# design.net
KiCad netlist of a schematic drawn in EasyEDA Pro
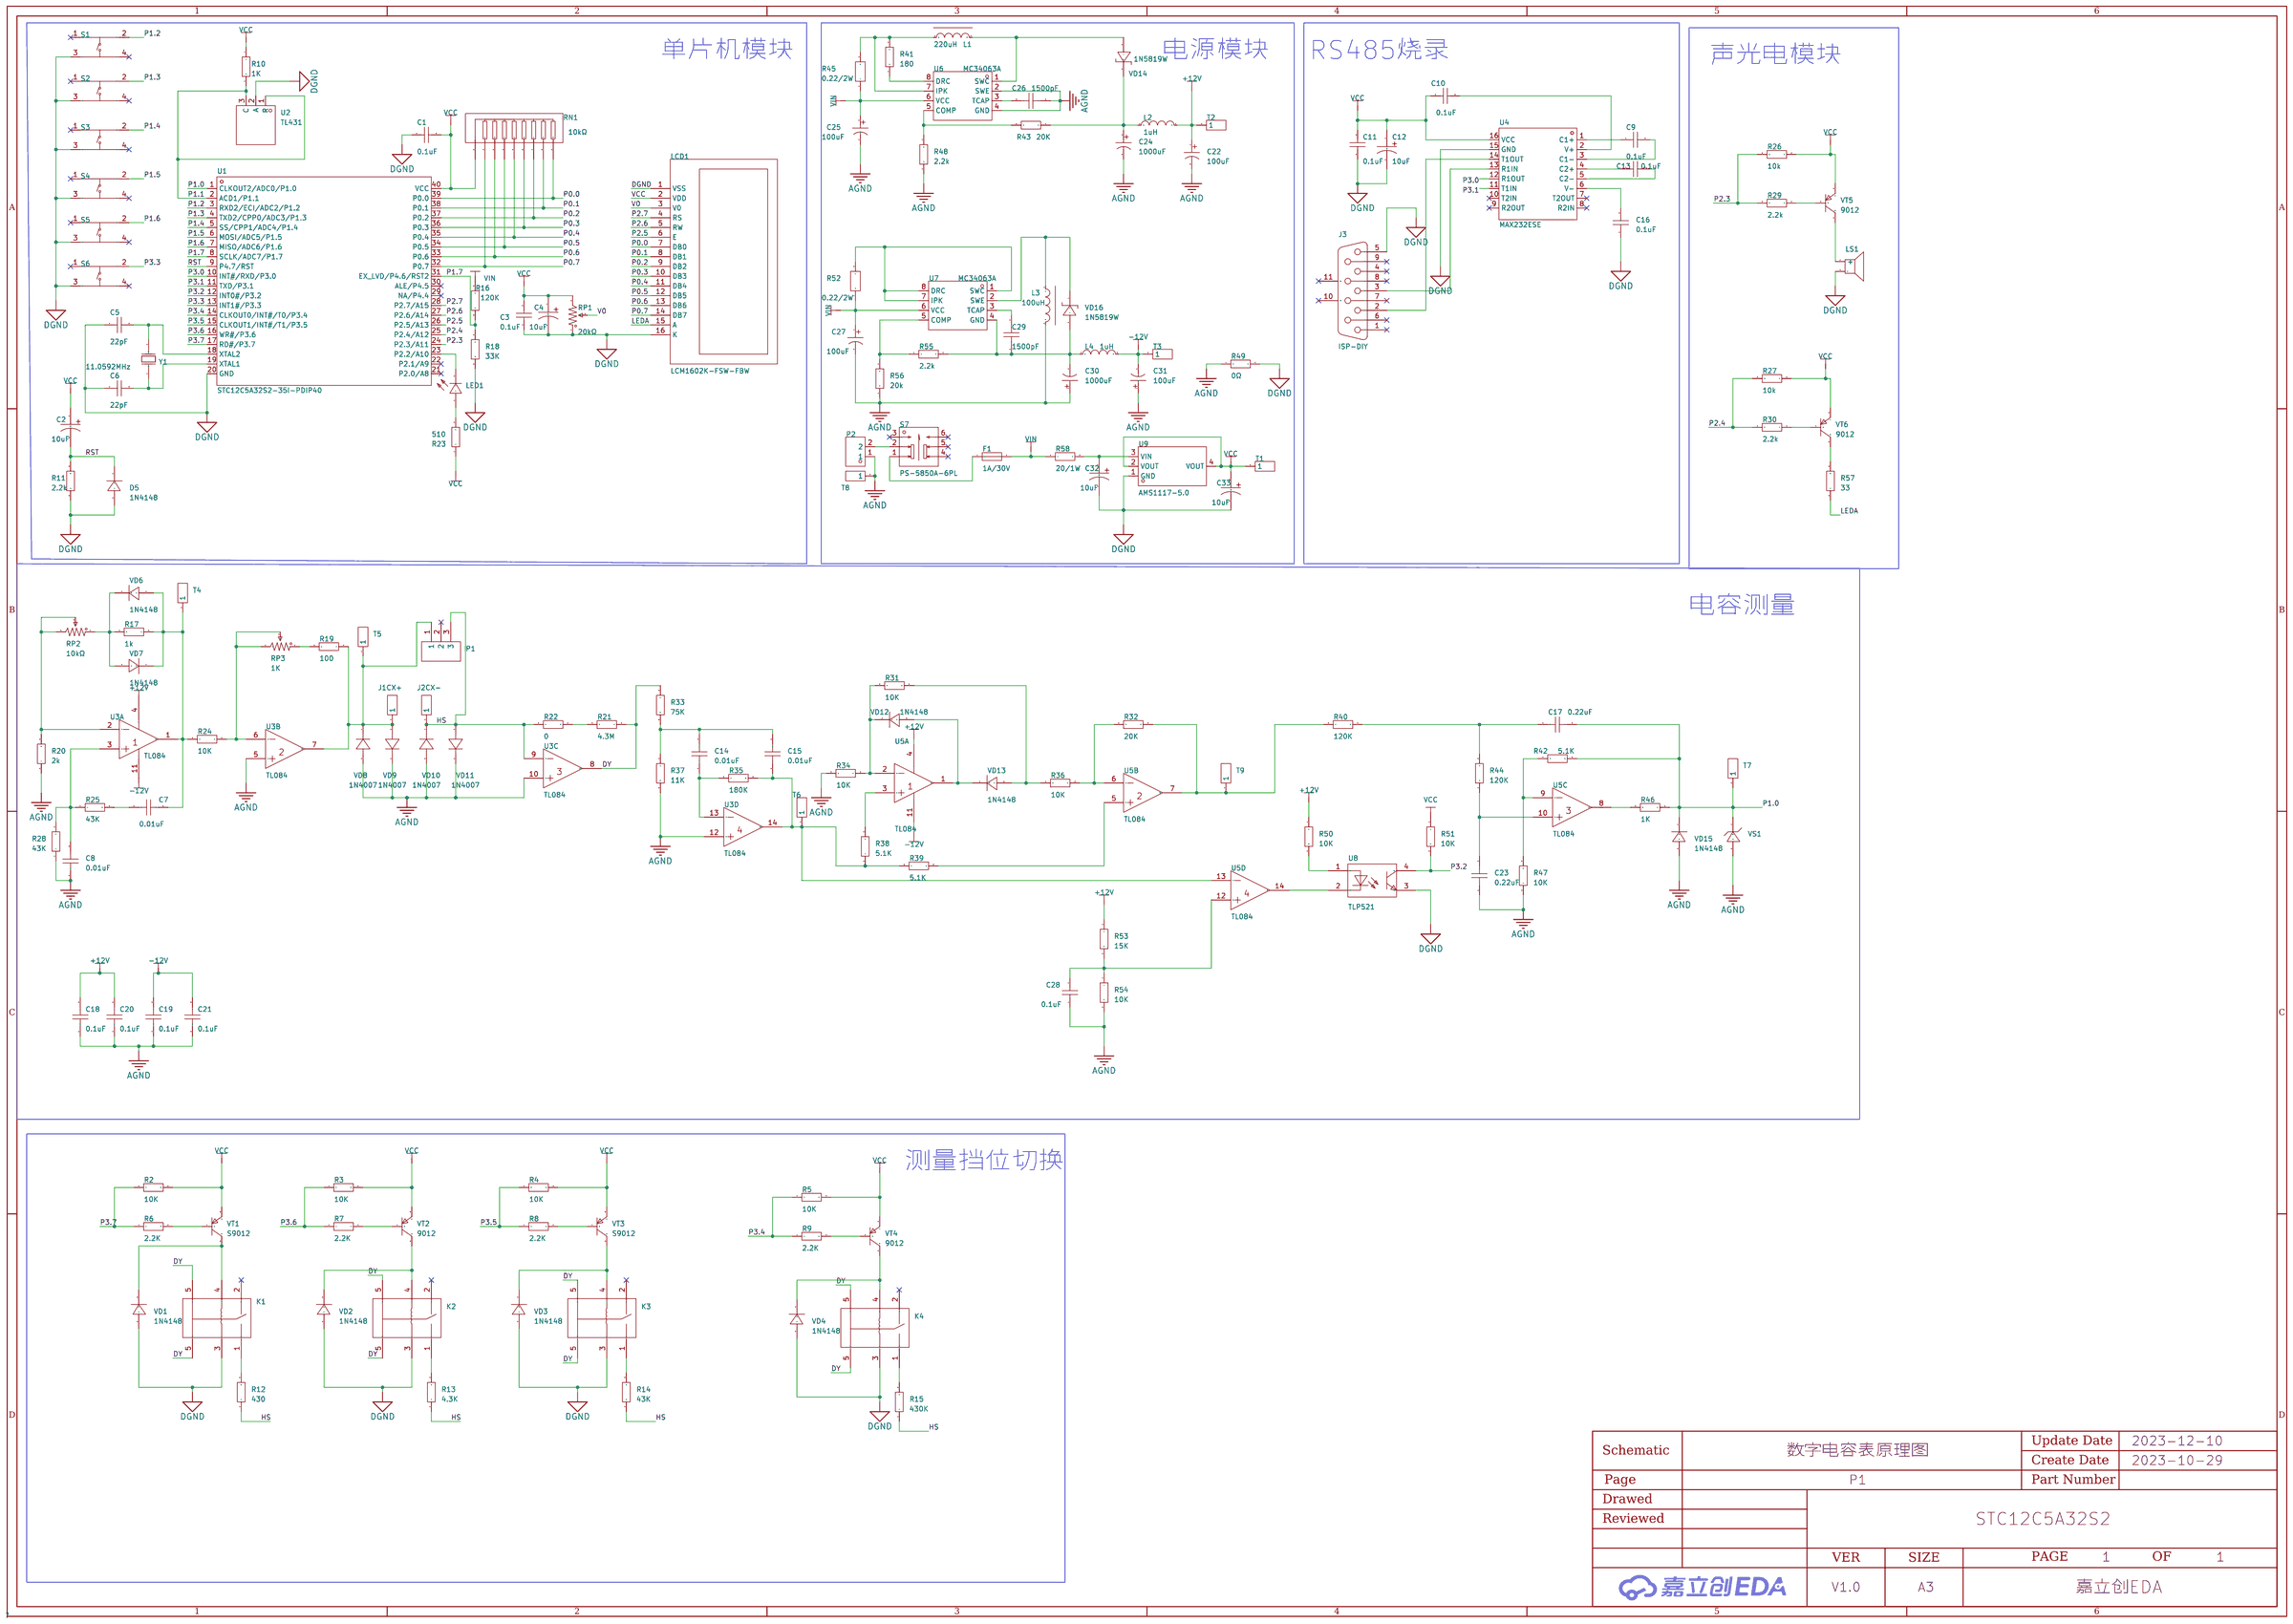
[diagram p0: schematic sheet]

(export (version "E")
  (design (tool "Eeschema 10.0.6"))
  (components
    (comp (ref "C1")
      (value "0.1uF")
      (footprint "easyedapro:C0805")
      (description "容值:100nF;精度:±10%;额定电压:50V;材质(温度系数):X7R;")
      (fields (field (name "Manufacturer Part") "C1608NP01H220J080AA") (field (name "Manufacturer") "TDK"))
      (libsource (lib "easyedapro") (part "0805B104K500NT"))
    )
    (comp (ref "C2")
      (value "10uF")
      (footprint "easyedapro:CAP-SMD_L3.2-W1.6")
      (description "容值:47uF;精度:±20%;额定电压:10V;等效串联电阻:2Ω@100kHz;")
      (fields (field (name "Manufacturer Part") "F931A476MAA") (field (name "Manufacturer") "Kyocera AVX"))
      (libsource (lib "easyedapro") (part "F931A476MAA"))
    )
    (comp (ref "C3")
      (value "0.1uF")
      (footprint "easyedapro:C0805")
      (description "容值:100nF;精度:±10%;额定电压:50V;材质(温度系数):X7R;")
      (fields (field (name "Manufacturer Part") "C1608NP01H220J080AA") (field (name "Manufacturer") "TDK"))
      (libsource (lib "easyedapro") (part "0805B104K500NT"))
    )
    (comp (ref "C4")
      (value "10uF")
      (footprint "easyedapro:CAP-SMD_L3.2-W1.6")
      (description "容值:47uF;精度:±20%;额定电压:10V;等效串联电阻:2Ω@100kHz;")
      (fields (field (name "Manufacturer Part") "F931A476MAA") (field (name "Manufacturer") "Kyocera AVX"))
      (libsource (lib "easyedapro") (part "F931A476MAA"))
    )
    (comp (ref "C5")
      (value "22pF")
      (footprint "easyedapro:C0805")
      (description "容值:100nF;精度:±10%;额定电压:50V;材质(温度系数):X7R;")
      (fields (field (name "Manufacturer Part") "C1608NP01H220J080AA") (field (name "Manufacturer") "TDK"))
      (libsource (lib "easyedapro") (part "0805B104K500NT"))
    )
    (comp (ref "C6")
      (value "22pF")
      (footprint "easyedapro:C0805")
      (description "容值:100nF;精度:±10%;额定电压:50V;材质(温度系数):X7R;")
      (fields (field (name "Manufacturer Part") "C1608NP01H220J080AA") (field (name "Manufacturer") "TDK"))
      (libsource (lib "easyedapro") (part "0805B104K500NT"))
    )
    (comp (ref "C7")
      (value "0.01uF")
      (footprint "easyedapro:CAP-TH_L13.0-W5.0-P10.00-D0.6")
      (description "容值:10nF;精度:±5%;额定电压:630V;")
      (fields
        (field (name "Manufacturer Part") "B1030630-D-10-3R")
        (field (name "Manufacturer") "GDHY(广东华裕)")
      )
      (libsource (lib "easyedapro") (part "B1030630-D-10-3R"))
    )
    (comp (ref "C8")
      (value "0.01uF")
      (footprint "easyedapro:CAP-TH_L10.3-W4.3-P7.50-D1.0")
      (description "容值:10nF;精度:±5%;额定电压:250V;")
      (fields (field (name "Manufacturer Part") "ECQE2103JF") (field (name "Manufacturer") "PANASONIC(松下)"))
      (libsource (lib "easyedapro") (part "ECQE2103JF"))
    )
    (comp (ref "C9")
      (value "0.1uF")
      (footprint "easyedapro:C0805")
      (description "容值:100nF;精度:±10%;额定电压:50V;材质(温度系数):X7R;")
      (fields (field (name "Manufacturer Part") "C1608NP01H220J080AA") (field (name "Manufacturer") "TDK"))
      (libsource (lib "easyedapro") (part "0805B104K500NT"))
    )
    (comp (ref "C10")
      (value "0.1uF")
      (footprint "easyedapro:C0805")
      (description "容值:100nF;精度:±10%;额定电压:50V;材质(温度系数):X7R;")
      (fields (field (name "Manufacturer Part") "C1608NP01H220J080AA") (field (name "Manufacturer") "TDK"))
      (libsource (lib "easyedapro") (part "0805B104K500NT"))
    )
    (comp (ref "C11")
      (value "0.1uF")
      (footprint "easyedapro:C0805")
      (description "容值:100nF;精度:±10%;额定电压:50V;材质(温度系数):X7R;")
      (fields (field (name "Manufacturer Part") "C1608NP01H220J080AA") (field (name "Manufacturer") "TDK"))
      (libsource (lib "easyedapro") (part "0805B104K500NT"))
    )
    (comp (ref "C12")
      (value "10uF")
      (footprint "easyedapro:CAP-SMD_L3.2-W1.6")
      (description "容值:47uF;精度:±20%;额定电压:10V;等效串联电阻:2Ω@100kHz;")
      (fields (field (name "Manufacturer Part") "F931A476MAA") (field (name "Manufacturer") "Kyocera AVX"))
      (libsource (lib "easyedapro") (part "F931A476MAA"))
    )
    (comp (ref "C13")
      (value "0.1uF")
      (footprint "easyedapro:C0805")
      (description "容值:100nF;精度:±10%;额定电压:50V;材质(温度系数):X7R;")
      (fields (field (name "Manufacturer Part") "C1608NP01H220J080AA") (field (name "Manufacturer") "TDK"))
      (libsource (lib "easyedapro") (part "0805B104K500NT"))
    )
    (comp (ref "C14")
      (value "0.01uF")
      (footprint "easyedapro:CAP-TH_L29.0-W17.5-P27.50-D0.8")
      (description "容值:10uF;精度:±5%;额定电压:250V;")
      (fields (field (name "Manufacturer Part") "KP106J2E2701") (field (name "Manufacturer") "KYET(科雅)"))
      (libsource (lib "easyedapro") (part "KP106J2E2701"))
    )
    (comp (ref "C15")
      (value "0.01uF")
      (footprint "easyedapro:CAP-TH_L29.0-W17.5-P27.50-D0.8")
      (description "容值:10uF;精度:±5%;额定电压:250V;")
      (fields (field (name "Manufacturer Part") "KP106J2E2701") (field (name "Manufacturer") "KYET(科雅)"))
      (libsource (lib "easyedapro") (part "KP106J2E2701"))
    )
    (comp (ref "C16")
      (value "0.1uF")
      (footprint "easyedapro:C0805")
      (description "容值:100nF;精度:±10%;额定电压:50V;材质(温度系数):X7R;")
      (fields (field (name "Manufacturer Part") "C1608NP01H220J080AA") (field (name "Manufacturer") "TDK"))
      (libsource (lib "easyedapro") (part "0805B104K500NT"))
    )
    (comp (ref "C17")
      (value "0.22uF")
      (footprint "easyedapro:CAP-TH_L29.0-W17.5-P27.50-D0.8")
      (description "容值:10uF;精度:±5%;额定电压:250V;")
      (fields (field (name "Manufacturer Part") "KP106J2E2701") (field (name "Manufacturer") "KYET(科雅)"))
      (libsource (lib "easyedapro") (part "KP106J2E2701"))
    )
    (comp (ref "C18")
      (value "0.1uF")
      (footprint "easyedapro:C0603")
      (description "容值:22pF;额定电压:50V;材质(温度系数):C0G;")
      (fields (field (name "Manufacturer Part") "0805B104K500NT") (field (name "Manufacturer") "FH(风华)"))
      (libsource (lib "easyedapro") (part "C1608NP01H220J080AA"))
    )
    (comp (ref "C19")
      (value "0.1uF")
      (footprint "easyedapro:C0603")
      (description "容值:22pF;额定电压:50V;材质(温度系数):C0G;")
      (fields (field (name "Manufacturer Part") "0805B104K500NT") (field (name "Manufacturer") "FH(风华)"))
      (libsource (lib "easyedapro") (part "C1608NP01H220J080AA"))
    )
    (comp (ref "C20")
      (value "0.1uF")
      (footprint "easyedapro:C0603")
      (description "容值:22pF;额定电压:50V;材质(温度系数):C0G;")
      (fields (field (name "Manufacturer Part") "0805B104K500NT") (field (name "Manufacturer") "FH(风华)"))
      (libsource (lib "easyedapro") (part "C1608NP01H220J080AA"))
    )
    (comp (ref "C21")
      (value "0.1uF")
      (footprint "easyedapro:C0603")
      (description "容值:22pF;额定电压:50V;材质(温度系数):C0G;")
      (fields (field (name "Manufacturer Part") "0805B104K500NT") (field (name "Manufacturer") "FH(风华)"))
      (libsource (lib "easyedapro") (part "C1608NP01H220J080AA"))
    )
    (comp (ref "C22")
      (value "100uF")
      (footprint "easyedapro:CAP-TH_BD13.0-P5.00-D1.2-FD")
      (description "容值:1000uF;精度:±20%;额定电压:35V;")
      (fields
        (field (name "Manufacturer Part") "35YXJ1000M12.5X20")
        (field (name "Manufacturer") "rubycon(红宝石)")
      )
      (libsource (lib "easyedapro") (part "35YXJ1000M12.5X20"))
    )
    (comp (ref "C23")
      (value "0.22uF")
      (footprint "easyedapro:CAP-TH_L29.0-W17.5-P27.50-D0.8")
      (description "容值:10uF;精度:±5%;额定电压:250V;")
      (fields (field (name "Manufacturer Part") "KP106J2E2701") (field (name "Manufacturer") "KYET(科雅)"))
      (libsource (lib "easyedapro") (part "KP106J2E2701"))
    )
    (comp (ref "C24")
      (value "1000uF")
      (footprint "easyedapro:CAP-TH_BD13.0-P5.00-D1.2-FD")
      (description "容值:1000uF;精度:±20%;额定电压:35V;")
      (fields
        (field (name "Manufacturer Part") "35YXJ1000M12.5X20")
        (field (name "Manufacturer") "rubycon(红宝石)")
      )
      (libsource (lib "easyedapro") (part "35YXJ1000M12.5X20"))
    )
    (comp (ref "C25")
      (value "100uF")
      (footprint "easyedapro:CAP-TH_BD13.0-P5.00-D1.2-FD")
      (description "容值:1000uF;精度:±20%;额定电压:35V;")
      (fields
        (field (name "Manufacturer Part") "35YXJ1000M12.5X20")
        (field (name "Manufacturer") "rubycon(红宝石)")
      )
      (libsource (lib "easyedapro") (part "35YXJ1000M12.5X20"))
    )
    (comp (ref "C26")
      (value "1500pF")
      (footprint "easyedapro:CAP-TH_L8.5-W5.0-P5.00-D1.2")
      (description "容值:100nF;精度:±10%;额定电压:250V;温度系数:X7R;")
      (fields (field (name "Manufacturer Part") "CT4-1206B104K251F3") (field (name "Manufacturer") "FH(风华)"))
      (libsource (lib "easyedapro") (part "CT4-1206B104K251F3"))
    )
    (comp (ref "C27")
      (value "100uF")
      (footprint "easyedapro:CAP-TH_BD6.3-P2.50-D1.0-FD")
      (description "容值:100uF;精度:±20%;额定电压:25V;纹波电流:95mA@120Hz;等效串联电阻:-;")
      (fields
        (field (name "Manufacturer Part") "KS107M025E07RR0VH2FP0")
        (field (name "Manufacturer") "CX(承兴)")
      )
      (libsource (lib "easyedapro") (part "100uF 25V 6.3*7"))
    )
    (comp (ref "C28")
      (value "0.1uF")
      (footprint "easyedapro:C0805")
      (description "容值:100nF;精度:±10%;额定电压:50V;材质(温度系数):X7R;")
      (fields (field (name "Manufacturer Part") "C1608NP01H220J080AA") (field (name "Manufacturer") "TDK"))
      (libsource (lib "easyedapro") (part "0805B104K500NT"))
    )
    (comp (ref "C29")
      (value "1500pF")
      (footprint "easyedapro:CAP-TH_L8.5-W5.0-P5.00-D1.2")
      (description "容值:100nF;精度:±10%;额定电压:250V;温度系数:X7R;")
      (fields (field (name "Manufacturer Part") "CT4-1206B104K251F3") (field (name "Manufacturer") "FH(风华)"))
      (libsource (lib "easyedapro") (part "CT4-1206B104K251F3"))
    )
    (comp (ref "C30")
      (value "1000uF")
      (footprint "easyedapro:CAP-TH_BD10.0-P5.00-D1.0-FD")
      (description "容值:1000uF;精度:±20%;额定电压:25V;纹波电流:870mA@120Hz;等效串联电阻:-;")
      (fields
        (field (name "Manufacturer Part") "25PK1000MEFC10*16")
        (field (name "Manufacturer") "rubycon(红宝石)")
      )
      (libsource (lib "easyedapro") (part "25PK1000MEFC10*16"))
    )
    (comp (ref "C31")
      (value "100uF")
      (footprint "easyedapro:CAP-TH_BD13.0-P5.00-D1.2-FD")
      (description "容值:1000uF;精度:±20%;额定电压:35V;")
      (fields
        (field (name "Manufacturer Part") "35YXJ1000M12.5X20")
        (field (name "Manufacturer") "rubycon(红宝石)")
      )
      (libsource (lib "easyedapro") (part "35YXJ1000M12.5X20"))
    )
    (comp (ref "C32")
      (value "10uF")
      (footprint "easyedapro:CAP-SMD_L3.2-W1.6")
      (description "容值:47uF;精度:±20%;额定电压:10V;等效串联电阻:2Ω@100kHz;")
      (fields (field (name "Manufacturer Part") "F931A476MAA") (field (name "Manufacturer") "Kyocera AVX"))
      (libsource (lib "easyedapro") (part "F931A476MAA"))
    )
    (comp (ref "C33")
      (value "10uF")
      (footprint "easyedapro:CAP-SMD_L3.2-W1.6")
      (description "容值:47uF;精度:±20%;额定电压:10V;等效串联电阻:2Ω@100kHz;")
      (fields (field (name "Manufacturer Part") "F931A476MAA") (field (name "Manufacturer") "Kyocera AVX"))
      (libsource (lib "easyedapro") (part "F931A476MAA"))
    )
    (comp (ref "D5")
      (value "1N4148")
      (footprint "easyedapro:DO-35_BD2.0-L4.0-P8.00-D0.5-FD")
      (fields (field (name "Manufacturer") "ST(先科)"))
      (libsource (lib "easyedapro") (part "1N4148"))
    )
    (comp (ref "F1")
      (value "1A/30V")
      (footprint "easyedapro:FUSE-TH_L7.4-W3.1-P5.08-D1.2")
      (description "最大电压:30V;最大电流:40A;保持电流:1.35A;跳闸电流:1.7A;")
      (fields (field (name "Manufacturer") "JK(金科)"))
      (libsource (lib "easyedapro") (part "JK30-135_C369101"))
    )
    (comp (ref "J1")
      (value "J1CX+")
      (footprint "easyedapro:HDR-TH_1P-V-M_XKB_X4611WV-01I-C28D40")
      (libsource (lib "easyedapro") (part "HDR_1x1"))
    )
    (comp (ref "J2")
      (value "J2CX-")
      (footprint "easyedapro:HDR-TH_1P-V-M_XKB_X4611WV-01I-C28D40")
      (libsource (lib "easyedapro") (part "HDR_1x1"))
    )
    (comp (ref "J3")
      (value "ISP-DIY")
      (footprint "easyedapro:DSUB-TH_DMR-9S")
      (description "连接器类型:D-Sub;公母:母;总PIN位数:9;排数:2;安装方式:弯插;额定电流:3A;工作温度范围:-50°C~+105°C;")
      (fields (field (name "Manufacturer") "Ckmtw(灿科盟)"))
      (libsource (lib "easyedapro") (part "DMR-9S"))
    )
    (comp (ref "K1")
      (value "HK4100F-DC5V-SHG")
      (footprint "easyedapro:RELAY-TH_HK4100F-DC5V-SHG")
      (description "线圈电压:-;线圈类型:-;触点形式:-;最大切换电流:-;触点材料:-;")
      (fields (field (name "Manufacturer") "汇科"))
      (libsource (lib "easyedapro") (part "HK4100F-DC5V-SHG"))
    )
    (comp (ref "K2")
      (value "HK4100F-DC5V-SHG")
      (footprint "easyedapro:RELAY-TH_HK4100F-DC5V-SHG")
      (description "线圈电压:-;线圈类型:-;触点形式:-;最大切换电流:-;触点材料:-;")
      (fields (field (name "Manufacturer") "汇科"))
      (libsource (lib "easyedapro") (part "HK4100F-DC5V-SHG"))
    )
    (comp (ref "K3")
      (value "HK4100F-DC5V-SHG")
      (footprint "easyedapro:RELAY-TH_HK4100F-DC5V-SHG")
      (description "线圈电压:-;线圈类型:-;触点形式:-;最大切换电流:-;触点材料:-;")
      (fields (field (name "Manufacturer") "汇科"))
      (libsource (lib "easyedapro") (part "HK4100F-DC5V-SHG"))
    )
    (comp (ref "K4")
      (value "HK4100F-DC5V-SHG")
      (footprint "easyedapro:RELAY-TH_HK4100F-DC5V-SHG")
      (description "线圈电压:-;线圈类型:-;触点形式:-;最大切换电流:-;触点材料:-;")
      (fields (field (name "Manufacturer") "汇科"))
      (libsource (lib "easyedapro") (part "HK4100F-DC5V-SHG"))
    )
    (comp (ref "L1")
      (value "220uH")
      (footprint "easyedapro:IND-TH_BD9.0-P5.00-D0.7")
      (description "电感值:220uH;精度:±20%;额定电流:600mA;")
      (fields (field (name "Manufacturer Part") "PK0810-221MB") (field (name "Manufacturer") "SXN(顺翔诺)"))
      (libsource (lib "easyedapro") (part "PK0810-221MB"))
    )
    (comp (ref "L2")
      (value "1uH")
      (footprint "easyedapro:IND-TH_BD5.0-L10.5-P14.50-D0.6")
      (description "类型:色环电感;电感值:1mH;精度:±10%;额定电流:100mA;直流电阻(DCR):8Ω;Q值:50@0.252MHz;自谐频率:1MHz;")
      (fields
        (field (name "Manufacturer Part") "CKL0510-1mH/K-A-0.252MHz T")
        (field (name "Manufacturer") "CENKER(岑科)")
      )
      (libsource (lib "easyedapro") (part "CKL0510-1MH/K-A-0.252MHZ T"))
    )
    (comp (ref "L3")
      (value "100uH")
      (footprint "easyedapro:IND-TH_BD9.5-P5.00-D0.7")
      (description "电感值:1mH;精度:±10%;额定电流:360mA;")
      (fields (field (name "Manufacturer Part") "VLU0810-102K") (field (name "Manufacturer") "FH(风华)"))
      (libsource (lib "easyedapro") (part "VLU0810-102K"))
    )
    (comp (ref "L4")
      (value "1uH")
      (footprint "easyedapro:IND-TH_BD5.0-L10.5-P14.50-D0.6")
      (description "类型:色环电感;电感值:1mH;精度:±10%;额定电流:100mA;直流电阻(DCR):8Ω;Q值:50@0.252MHz;自谐频率:1MHz;")
      (fields
        (field (name "Manufacturer Part") "CKL0510-1mH/K-A-0.252MHz T")
        (field (name "Manufacturer") "CENKER(岑科)")
      )
      (libsource (lib "easyedapro") (part "CKL0510-1MH/K-A-0.252MHZ T"))
    )
    (comp (ref "LCD1")
      (value "LCM1602K-FSW-FBW")
      (footprint "easyedapro:MODULE-TH_LCM1602K")
      (description "尺寸(inch):-;主控芯片:KS0066U;")
      (fields (field (name "Manufacturer") "LONTECH(厦门龙特)"))
      (libsource (lib "easyedapro") (part "LCM1602K-FSW-FBW"))
    )
    (comp (ref "LED1")
      (value "204-10SUGD/S400-A5")
      (footprint "easyedapro:LED-TH_BD3.0-P2.54-FD")
      (description "发光颜色:翠绿;二极管配置:-;主波长:530nm;色温:-;功率:110mW;安装方式:-;")
      (fields (field (name "Manufacturer") "EVERLIGHT(亿光)"))
      (libsource (lib "easyedapro") (part "204-10SUGD/S400-A5"))
    )
    (comp (ref "LS1")
      (value "2.3kHz")
      (footprint "easyedapro:BUZ-TH_BD12.0-P7.60-D0.6-FD")
      (description "驱动方式:有源(内含驱动线路);构造类型:电磁式;额定电压:5V;频率:2.3kHz;声压(SPL):85dB@5V,10cm;")
      (fields (field (name "Manufacturer Part") "TMB12A05") (field (name "Manufacturer") "华能"))
      (libsource (lib "easyedapro") (part "TMB12A05"))
    )
    (comp (ref "P1")
      (value "B3B-XH-A(LF)(SN)")
      (footprint "easyedapro:CONN-TH_3P-P2.50_A2501WV2-3P")
      (description "参考系列:XH;间距:2.5mm;插针结构:1x3P;排数:1;每排PIN数:3;行距:-;安装方式:-;触头材质:黄铜;")
      (fields (field (name "Manufacturer") "JST"))
      (libsource (lib "easyedapro") (part "B3B-XH-A(LF)(SN)"))
    )
    (comp (ref "P2")
      (value "PZ254V-11-02P")
      (footprint "easyedapro:HDR-TH_2P-P2.54-V-M")
      (fields (field (name "Manufacturer") "XFCN(兴飞)"))
      (libsource (lib "easyedapro") (part "PZ254V-11-02P"))
    )
    (comp (ref "R2")
      (value "10K")
      (footprint "easyedapro:R0805")
      (description "电阻类型:金属膜电阻;阻值:505Ω;精度:±0.1%;功率:125mW;")
      (fields (field (name "Manufacturer Part") "RN73H2ATTD5050B10") (field (name "Manufacturer") "KOA"))
      (libsource (lib "easyedapro") (part "RN73H2ATTD5050B10"))
    )
    (comp (ref "R3")
      (value "10K")
      (footprint "easyedapro:R0805")
      (description "电阻类型:金属膜电阻;阻值:505Ω;精度:±0.1%;功率:125mW;")
      (fields (field (name "Manufacturer Part") "RN73H2ATTD5050B10") (field (name "Manufacturer") "KOA"))
      (libsource (lib "easyedapro") (part "RN73H2ATTD5050B10"))
    )
    (comp (ref "R4")
      (value "10K")
      (footprint "easyedapro:R0805")
      (description "电阻类型:金属膜电阻;阻值:505Ω;精度:±0.1%;功率:125mW;")
      (fields (field (name "Manufacturer Part") "RN73H2ATTD5050B10") (field (name "Manufacturer") "KOA"))
      (libsource (lib "easyedapro") (part "RN73H2ATTD5050B10"))
    )
    (comp (ref "R5")
      (value "10K")
      (footprint "easyedapro:R0805")
      (description "电阻类型:金属膜电阻;阻值:505Ω;精度:±0.1%;功率:125mW;")
      (fields (field (name "Manufacturer Part") "RN73H2ATTD5050B10") (field (name "Manufacturer") "KOA"))
      (libsource (lib "easyedapro") (part "RN73H2ATTD5050B10"))
    )
    (comp (ref "R6")
      (value "2.2K")
      (footprint "easyedapro:R0805")
      (description "电阻类型:金属膜电阻;阻值:505Ω;精度:±0.1%;功率:125mW;")
      (fields (field (name "Manufacturer Part") "RN73H2ATTD5050B10") (field (name "Manufacturer") "KOA"))
      (libsource (lib "easyedapro") (part "RN73H2ATTD5050B10"))
    )
    (comp (ref "R7")
      (value "2.2K")
      (footprint "easyedapro:R0805")
      (description "电阻类型:金属膜电阻;阻值:505Ω;精度:±0.1%;功率:125mW;")
      (fields (field (name "Manufacturer Part") "RN73H2ATTD5050B10") (field (name "Manufacturer") "KOA"))
      (libsource (lib "easyedapro") (part "RN73H2ATTD5050B10"))
    )
    (comp (ref "R8")
      (value "2.2K")
      (footprint "easyedapro:R0805")
      (description "电阻类型:金属膜电阻;阻值:505Ω;精度:±0.1%;功率:125mW;")
      (fields (field (name "Manufacturer Part") "RN73H2ATTD5050B10") (field (name "Manufacturer") "KOA"))
      (libsource (lib "easyedapro") (part "RN73H2ATTD5050B10"))
    )
    (comp (ref "R9")
      (value "2.2K")
      (footprint "easyedapro:R0805")
      (description "电阻类型:金属膜电阻;阻值:505Ω;精度:±0.1%;功率:125mW;")
      (fields (field (name "Manufacturer Part") "RN73H2ATTD5050B10") (field (name "Manufacturer") "KOA"))
      (libsource (lib "easyedapro") (part "RN73H2ATTD5050B10"))
    )
    (comp (ref "R10")
      (value "1K")
      (footprint "easyedapro:R0805")
      (description "电阻类型:金属膜电阻;阻值:505Ω;精度:±0.1%;功率:125mW;")
      (fields (field (name "Manufacturer Part") "RN73H2ATTD5050B10") (field (name "Manufacturer") "KOA"))
      (libsource (lib "easyedapro") (part "RN73H2ATTD5050B10"))
    )
    (comp (ref "R11")
      (value "2.2k")
      (footprint "easyedapro:R0805")
      (description "电阻类型:金属膜电阻;阻值:505Ω;精度:±0.1%;功率:125mW;")
      (fields (field (name "Manufacturer Part") "RN73H2ATTD5050B10") (field (name "Manufacturer") "KOA"))
      (libsource (lib "easyedapro") (part "RN73H2ATTD5050B10"))
    )
    (comp (ref "R12")
      (value "430")
      (footprint "easyedapro:R0805")
      (description "电阻类型:金属膜电阻;阻值:505Ω;精度:±0.1%;功率:125mW;")
      (fields (field (name "Manufacturer Part") "RN73H2ATTD5050B10") (field (name "Manufacturer") "KOA"))
      (libsource (lib "easyedapro") (part "RN73H2ATTD5050B10"))
    )
    (comp (ref "R13")
      (value "4.3K")
      (footprint "easyedapro:R0805")
      (description "电阻类型:金属膜电阻;阻值:505Ω;精度:±0.1%;功率:125mW;")
      (fields (field (name "Manufacturer Part") "RN73H2ATTD5050B10") (field (name "Manufacturer") "KOA"))
      (libsource (lib "easyedapro") (part "RN73H2ATTD5050B10"))
    )
    (comp (ref "R14")
      (value "43K")
      (footprint "easyedapro:R0805")
      (description "电阻类型:金属膜电阻;阻值:505Ω;精度:±0.1%;功率:125mW;")
      (fields (field (name "Manufacturer Part") "RN73H2ATTD5050B10") (field (name "Manufacturer") "KOA"))
      (libsource (lib "easyedapro") (part "RN73H2ATTD5050B10"))
    )
    (comp (ref "R15")
      (value "430K")
      (footprint "easyedapro:R0805")
      (description "电阻类型:金属膜电阻;阻值:505Ω;精度:±0.1%;功率:125mW;")
      (fields (field (name "Manufacturer Part") "RN73H2ATTD5050B10") (field (name "Manufacturer") "KOA"))
      (libsource (lib "easyedapro") (part "RN73H2ATTD5050B10"))
    )
    (comp (ref "R16")
      (value "120K")
      (footprint "easyedapro:R0805")
      (description "电阻类型:金属膜电阻;阻值:505Ω;精度:±0.1%;功率:125mW;")
      (fields (field (name "Manufacturer Part") "RN73H2ATTD5050B10") (field (name "Manufacturer") "KOA"))
      (libsource (lib "easyedapro") (part "RN73H2ATTD5050B10"))
    )
    (comp (ref "R17")
      (value "1k")
      (footprint "easyedapro:R0805")
      (description "电阻类型:金属膜电阻;阻值:505Ω;精度:±0.1%;功率:125mW;")
      (fields (field (name "Manufacturer Part") "RN73H2ATTD5050B10") (field (name "Manufacturer") "KOA"))
      (libsource (lib "easyedapro") (part "RN73H2ATTD5050B10"))
    )
    (comp (ref "R18")
      (value "33K")
      (footprint "easyedapro:R0805")
      (description "电阻类型:金属膜电阻;阻值:505Ω;精度:±0.1%;功率:125mW;")
      (fields (field (name "Manufacturer Part") "RN73H2ATTD5050B10") (field (name "Manufacturer") "KOA"))
      (libsource (lib "easyedapro") (part "RN73H2ATTD5050B10"))
    )
    (comp (ref "R19")
      (value "100")
      (footprint "easyedapro:R0805")
      (description "电阻类型:金属膜电阻;阻值:505Ω;精度:±0.1%;功率:125mW;")
      (fields (field (name "Manufacturer Part") "RN73H2ATTD5050B10") (field (name "Manufacturer") "KOA"))
      (libsource (lib "easyedapro") (part "RN73H2ATTD5050B10"))
    )
    (comp (ref "R20")
      (value "2k")
      (footprint "easyedapro:R0805")
      (description "电阻类型:金属膜电阻;阻值:505Ω;精度:±0.1%;功率:125mW;")
      (fields (field (name "Manufacturer Part") "RN73H2ATTD5050B10") (field (name "Manufacturer") "KOA"))
      (libsource (lib "easyedapro") (part "RN73H2ATTD5050B10"))
    )
    (comp (ref "R21")
      (value "4.3M")
      (footprint "easyedapro:R0805")
      (description "电阻类型:金属膜电阻;阻值:505Ω;精度:±0.1%;功率:125mW;")
      (fields (field (name "Manufacturer Part") "RN73H2ATTD5050B10") (field (name "Manufacturer") "KOA"))
      (libsource (lib "easyedapro") (part "RN73H2ATTD5050B10"))
    )
    (comp (ref "R22")
      (value "0")
      (footprint "easyedapro:R0805")
      (description "电阻类型:金属膜电阻;阻值:505Ω;精度:±0.1%;功率:125mW;")
      (fields (field (name "Manufacturer Part") "RN73H2ATTD5050B10") (field (name "Manufacturer") "KOA"))
      (libsource (lib "easyedapro") (part "RN73H2ATTD5050B10"))
    )
    (comp (ref "R23")
      (value "510")
      (footprint "easyedapro:R0805")
      (description "电阻类型:金属膜电阻;阻值:505Ω;精度:±0.1%;功率:125mW;")
      (fields (field (name "Manufacturer Part") "RN73H2ATTD5050B10") (field (name "Manufacturer") "KOA"))
      (libsource (lib "easyedapro") (part "RN73H2ATTD5050B10"))
    )
    (comp (ref "R24")
      (value "10K")
      (footprint "easyedapro:R0805")
      (description "电阻类型:金属膜电阻;阻值:505Ω;精度:±0.1%;功率:125mW;")
      (fields (field (name "Manufacturer Part") "RN73H2ATTD5050B10") (field (name "Manufacturer") "KOA"))
      (libsource (lib "easyedapro") (part "RN73H2ATTD5050B10"))
    )
    (comp (ref "R25")
      (value "43K")
      (footprint "easyedapro:R0805")
      (description "电阻类型:金属膜电阻;阻值:505Ω;精度:±0.1%;功率:125mW;")
      (fields (field (name "Manufacturer Part") "RN73H2ATTD5050B10") (field (name "Manufacturer") "KOA"))
      (libsource (lib "easyedapro") (part "RN73H2ATTD5050B10"))
    )
    (comp (ref "R26")
      (value "10k")
      (footprint "easyedapro:R0805")
      (description "电阻类型:金属膜电阻;阻值:505Ω;精度:±0.1%;功率:125mW;")
      (fields (field (name "Manufacturer Part") "RN73H2ATTD5050B10") (field (name "Manufacturer") "KOA"))
      (libsource (lib "easyedapro") (part "RN73H2ATTD5050B10"))
    )
    (comp (ref "R27")
      (value "10k")
      (footprint "easyedapro:R0805")
      (description "电阻类型:金属膜电阻;阻值:505Ω;精度:±0.1%;功率:125mW;")
      (fields (field (name "Manufacturer Part") "RN73H2ATTD5050B10") (field (name "Manufacturer") "KOA"))
      (libsource (lib "easyedapro") (part "RN73H2ATTD5050B10"))
    )
    (comp (ref "R28")
      (value "43K")
      (footprint "easyedapro:R0805")
      (description "电阻类型:金属膜电阻;阻值:505Ω;精度:±0.1%;功率:125mW;")
      (fields (field (name "Manufacturer Part") "RN73H2ATTD5050B10") (field (name "Manufacturer") "KOA"))
      (libsource (lib "easyedapro") (part "RN73H2ATTD5050B10"))
    )
    (comp (ref "R29")
      (value "2.2k")
      (footprint "easyedapro:R0805")
      (description "电阻类型:金属膜电阻;阻值:505Ω;精度:±0.1%;功率:125mW;")
      (fields (field (name "Manufacturer Part") "RN73H2ATTD5050B10") (field (name "Manufacturer") "KOA"))
      (libsource (lib "easyedapro") (part "RN73H2ATTD5050B10"))
    )
    (comp (ref "R30")
      (value "2.2k")
      (footprint "easyedapro:R0805")
      (description "电阻类型:金属膜电阻;阻值:505Ω;精度:±0.1%;功率:125mW;")
      (fields (field (name "Manufacturer Part") "RN73H2ATTD5050B10") (field (name "Manufacturer") "KOA"))
      (libsource (lib "easyedapro") (part "RN73H2ATTD5050B10"))
    )
    (comp (ref "R31")
      (value "10K")
      (footprint "easyedapro:R0805")
      (description "电阻类型:金属膜电阻;阻值:505Ω;精度:±0.1%;功率:125mW;")
      (fields (field (name "Manufacturer Part") "RN73H2ATTD5050B10") (field (name "Manufacturer") "KOA"))
      (libsource (lib "easyedapro") (part "RN73H2ATTD5050B10"))
    )
    (comp (ref "R32")
      (value "20K")
      (footprint "easyedapro:R0805")
      (description "电阻类型:金属膜电阻;阻值:505Ω;精度:±0.1%;功率:125mW;")
      (fields (field (name "Manufacturer Part") "RN73H2ATTD5050B10") (field (name "Manufacturer") "KOA"))
      (libsource (lib "easyedapro") (part "RN73H2ATTD5050B10"))
    )
    (comp (ref "R33")
      (value "75K")
      (footprint "easyedapro:R0805")
      (description "电阻类型:金属膜电阻;阻值:505Ω;精度:±0.1%;功率:125mW;")
      (fields (field (name "Manufacturer Part") "RN73H2ATTD5050B10") (field (name "Manufacturer") "KOA"))
      (libsource (lib "easyedapro") (part "RN73H2ATTD5050B10"))
    )
    (comp (ref "R34")
      (value "10K")
      (footprint "easyedapro:R0805")
      (description "电阻类型:金属膜电阻;阻值:505Ω;精度:±0.1%;功率:125mW;")
      (fields (field (name "Manufacturer Part") "RN73H2ATTD5050B10") (field (name "Manufacturer") "KOA"))
      (libsource (lib "easyedapro") (part "RN73H2ATTD5050B10"))
    )
    (comp (ref "R35")
      (value "180K")
      (footprint "easyedapro:R0805")
      (description "电阻类型:金属膜电阻;阻值:505Ω;精度:±0.1%;功率:125mW;")
      (fields (field (name "Manufacturer Part") "RN73H2ATTD5050B10") (field (name "Manufacturer") "KOA"))
      (libsource (lib "easyedapro") (part "RN73H2ATTD5050B10"))
    )
    (comp (ref "R36")
      (value "10K")
      (footprint "easyedapro:R0805")
      (description "电阻类型:金属膜电阻;阻值:505Ω;精度:±0.1%;功率:125mW;")
      (fields (field (name "Manufacturer Part") "RN73H2ATTD5050B10") (field (name "Manufacturer") "KOA"))
      (libsource (lib "easyedapro") (part "RN73H2ATTD5050B10"))
    )
    (comp (ref "R37")
      (value "11K")
      (footprint "easyedapro:R0805")
      (description "电阻类型:金属膜电阻;阻值:505Ω;精度:±0.1%;功率:125mW;")
      (fields (field (name "Manufacturer Part") "RN73H2ATTD5050B10") (field (name "Manufacturer") "KOA"))
      (libsource (lib "easyedapro") (part "RN73H2ATTD5050B10"))
    )
    (comp (ref "R38")
      (value "5.1K")
      (footprint "easyedapro:R0805")
      (description "电阻类型:金属膜电阻;阻值:505Ω;精度:±0.1%;功率:125mW;")
      (fields (field (name "Manufacturer Part") "RN73H2ATTD5050B10") (field (name "Manufacturer") "KOA"))
      (libsource (lib "easyedapro") (part "RN73H2ATTD5050B10"))
    )
    (comp (ref "R39")
      (value "5.1K")
      (footprint "easyedapro:R0805")
      (description "电阻类型:金属膜电阻;阻值:505Ω;精度:±0.1%;功率:125mW;")
      (fields (field (name "Manufacturer Part") "RN73H2ATTD5050B10") (field (name "Manufacturer") "KOA"))
      (libsource (lib "easyedapro") (part "RN73H2ATTD5050B10"))
    )
    (comp (ref "R40")
      (value "120K")
      (footprint "easyedapro:R0805")
      (description "电阻类型:金属膜电阻;阻值:505Ω;精度:±0.1%;功率:125mW;")
      (fields (field (name "Manufacturer Part") "RN73H2ATTD5050B10") (field (name "Manufacturer") "KOA"))
      (libsource (lib "easyedapro") (part "RN73H2ATTD5050B10"))
    )
    (comp (ref "R41")
      (value "180")
      (footprint "easyedapro:R0805")
      (description "电阻类型:金属膜电阻;阻值:505Ω;精度:±0.1%;功率:125mW;")
      (fields (field (name "Manufacturer Part") "RN73H2ATTD5050B10") (field (name "Manufacturer") "KOA"))
      (libsource (lib "easyedapro") (part "RN73H2ATTD5050B10"))
    )
    (comp (ref "R42")
      (value "5.1K")
      (footprint "easyedapro:R0805")
      (description "电阻类型:金属膜电阻;阻值:505Ω;精度:±0.1%;功率:125mW;")
      (fields (field (name "Manufacturer Part") "RN73H2ATTD5050B10") (field (name "Manufacturer") "KOA"))
      (libsource (lib "easyedapro") (part "RN73H2ATTD5050B10"))
    )
    (comp (ref "R43")
      (value "20K")
      (footprint "easyedapro:R0805")
      (description "电阻类型:金属膜电阻;阻值:505Ω;精度:±0.1%;功率:125mW;")
      (fields (field (name "Manufacturer Part") "RN73H2ATTD5050B10") (field (name "Manufacturer") "KOA"))
      (libsource (lib "easyedapro") (part "RN73H2ATTD5050B10"))
    )
    (comp (ref "R44")
      (value "120K")
      (footprint "easyedapro:R0805")
      (description "电阻类型:金属膜电阻;阻值:505Ω;精度:±0.1%;功率:125mW;")
      (fields (field (name "Manufacturer Part") "RN73H2ATTD5050B10") (field (name "Manufacturer") "KOA"))
      (libsource (lib "easyedapro") (part "RN73H2ATTD5050B10"))
    )
    (comp (ref "R45")
      (value "0.22/2W")
      (footprint "easyedapro:RES-TH_BD5.0-L15.5-P19.50-D0.8")
      (description "电阻类型:绕线电阻;阻值:220mΩ;精度:±1%;功率:2W;温度系数:±400ppm/°C;")
      (fields
        (field (name "Manufacturer Part") "RN1/4W10KFT/BA1")
        (field (name "Manufacturer") "Tyohm(幸亚电阻)")
      )
      (libsource (lib "easyedapro") (part "NKNP2W-0Ω22±1%-9T73"))
    )
    (comp (ref "R46")
      (value "1K")
      (footprint "easyedapro:R0805")
      (description "电阻类型:金属膜电阻;阻值:505Ω;精度:±0.1%;功率:125mW;")
      (fields (field (name "Manufacturer Part") "RN73H2ATTD5050B10") (field (name "Manufacturer") "KOA"))
      (libsource (lib "easyedapro") (part "RN73H2ATTD5050B10"))
    )
    (comp (ref "R47")
      (value "10K")
      (footprint "easyedapro:R0805")
      (description "电阻类型:金属膜电阻;阻值:505Ω;精度:±0.1%;功率:125mW;")
      (fields (field (name "Manufacturer Part") "RN73H2ATTD5050B10") (field (name "Manufacturer") "KOA"))
      (libsource (lib "easyedapro") (part "RN73H2ATTD5050B10"))
    )
    (comp (ref "R48")
      (value "2.2k")
      (footprint "easyedapro:R0805")
      (description "电阻类型:金属膜电阻;阻值:505Ω;精度:±0.1%;功率:125mW;")
      (fields (field (name "Manufacturer Part") "RN73H2ATTD5050B10") (field (name "Manufacturer") "KOA"))
      (libsource (lib "easyedapro") (part "RN73H2ATTD5050B10"))
    )
    (comp (ref "R49")
      (value "0Ω")
      (footprint "easyedapro:RES-TH_BD2.4-L6.3-P10.30-D0.6")
      (description "电阻类型:金属膜电阻;阻值:0Ω;功率:250mW;")
      (fields (field (name "Manufacturer Part") "MFR-25-T-52-0R") (field (name "Manufacturer") "YAGEO(国巨)"))
      (libsource (lib "easyedapro") (part "MFR-25-T-52-0R"))
    )
    (comp (ref "R50")
      (value "10K")
      (footprint "easyedapro:R0805")
      (description "电阻类型:金属膜电阻;阻值:505Ω;精度:±0.1%;功率:125mW;")
      (fields (field (name "Manufacturer Part") "RN73H2ATTD5050B10") (field (name "Manufacturer") "KOA"))
      (libsource (lib "easyedapro") (part "RN73H2ATTD5050B10"))
    )
    (comp (ref "R51")
      (value "10K")
      (footprint "easyedapro:R0805")
      (description "电阻类型:金属膜电阻;阻值:505Ω;精度:±0.1%;功率:125mW;")
      (fields (field (name "Manufacturer Part") "RN73H2ATTD5050B10") (field (name "Manufacturer") "KOA"))
      (libsource (lib "easyedapro") (part "RN73H2ATTD5050B10"))
    )
    (comp (ref "R52")
      (value "0.22/2W")
      (footprint "easyedapro:RES-TH_BD2.4-L6.3-P10.30-D0.6")
      (description "电阻类型:金属膜电阻;阻值:10kΩ;精度:±1%;功率:250mW;温度系数:±50ppm/°C;最大工作电压:250V;工作温度范围:-55°C~+125°C;")
      (fields
        (field (name "Manufacturer Part") "RN1/4W10KFT/BA1")
        (field (name "Manufacturer") "Tyohm(幸亚电阻)")
      )
      (libsource (lib "easyedapro") (part "RN 1/4W 10K F T/B A1"))
    )
    (comp (ref "R53")
      (value "15K")
      (footprint "easyedapro:R0805")
      (description "电阻类型:金属膜电阻;阻值:505Ω;精度:±0.1%;功率:125mW;")
      (fields (field (name "Manufacturer Part") "RN73H2ATTD5050B10") (field (name "Manufacturer") "KOA"))
      (libsource (lib "easyedapro") (part "RN73H2ATTD5050B10"))
    )
    (comp (ref "R54")
      (value "10K")
      (footprint "easyedapro:R0805")
      (description "电阻类型:金属膜电阻;阻值:505Ω;精度:±0.1%;功率:125mW;")
      (fields (field (name "Manufacturer Part") "RN73H2ATTD5050B10") (field (name "Manufacturer") "KOA"))
      (libsource (lib "easyedapro") (part "RN73H2ATTD5050B10"))
    )
    (comp (ref "R55")
      (value "2.2k")
      (footprint "easyedapro:R0805")
      (description "电阻类型:金属膜电阻;阻值:505Ω;精度:±0.1%;功率:125mW;")
      (fields (field (name "Manufacturer Part") "RN73H2ATTD5050B10") (field (name "Manufacturer") "KOA"))
      (libsource (lib "easyedapro") (part "RN73H2ATTD5050B10"))
    )
    (comp (ref "R56")
      (value "20k")
      (footprint "easyedapro:R0805")
      (description "电阻类型:金属膜电阻;阻值:505Ω;精度:±0.1%;功率:125mW;")
      (fields (field (name "Manufacturer Part") "RN73H2ATTD5050B10") (field (name "Manufacturer") "KOA"))
      (libsource (lib "easyedapro") (part "RN73H2ATTD5050B10"))
    )
    (comp (ref "R57")
      (value "33")
      (footprint "easyedapro:R0805")
      (description "电阻类型:金属膜电阻;阻值:505Ω;精度:±0.1%;功率:125mW;")
      (fields (field (name "Manufacturer Part") "RN73H2ATTD5050B10") (field (name "Manufacturer") "KOA"))
      (libsource (lib "easyedapro") (part "RN73H2ATTD5050B10"))
    )
    (comp (ref "R58")
      (value "20/1W")
      (footprint "easyedapro:RES-TH_BD8.0-L24.5-P28.50-D0.8")
      (description "阻值:510mΩ;精度:±5%;功率:5W;")
      (fields (field (name "Manufacturer Part") "KNP5W-0Ω51±5%-CP") (field (name "Manufacturer") "VO(翔胜)"))
      (libsource (lib "easyedapro") (part "KNP5W-0Ω51±5%-CP"))
    )
    (comp (ref "RN1")
      (value "10kΩ")
      (footprint "easyedapro:RES-ARRAY-TH_9P-P2.54-D1.0")
      (description "阻值:10kΩ;精度:±5%;单个元件功率:125mW;电阻器数:8;")
      (fields (field (name "Manufacturer Part") "A09-103JP") (field (name "Manufacturer") "FH(风华)"))
      (libsource (lib "easyedapro") (part "A09-103JP"))
    )
    (comp (ref "RP1")
      (value "20kΩ")
      (footprint "easyedapro:RES-ADJ-TH_3P-L10.0-W10.0-P2.50-L")
      (description "阻值:10kΩ;精度:±10%;")
      (fields (field (name "Manufacturer Part") "3296W-1-103") (field (name "Manufacturer") "BOCHEN(博晨)"))
      (libsource (lib "easyedapro") (part "3296W-1-103"))
    )
    (comp (ref "RP2")
      (value "10kΩ")
      (footprint "easyedapro:RES-ADJ-TH_3P-L10.0-W10.0-P2.50-L")
      (description "阻值:10kΩ;精度:±10%;")
      (fields (field (name "Manufacturer Part") "3296W-1-103") (field (name "Manufacturer") "BOCHEN(博晨)"))
      (libsource (lib "easyedapro") (part "3296W-1-103"))
    )
    (comp (ref "RP3")
      (value "1K")
      (footprint "easyedapro:RES-ADJ-TH_3P-L10.0-W10.0-P2.50-L")
      (description "阻值:10kΩ;精度:±10%;")
      (fields (field (name "Manufacturer Part") "3296W-1-103") (field (name "Manufacturer") "BOCHEN(博晨)"))
      (libsource (lib "easyedapro") (part "3296W-1-103"))
    )
    (comp (ref "S1")
      (value "TS665CJ")
      (footprint "easyedapro:SW-TH_4P-L6.0-W6.0-P4.50-LS6.5")
      (description "触点电流:50mA;额定电压(DC):12V;电路结构:单刀单掷;安装方式:直插;带灯:-;机械寿命:-;")
      (fields (field (name "Manufacturer") "SHOU HAN(首韩)"))
      (libsource (lib "easyedapro") (part "TS665CJ"))
    )
    (comp (ref "S2")
      (value "TS665CJ")
      (footprint "easyedapro:SW-TH_4P-L6.0-W6.0-P4.50-LS6.5")
      (description "触点电流:50mA;额定电压(DC):12V;电路结构:单刀单掷;安装方式:直插;带灯:-;机械寿命:-;")
      (fields (field (name "Manufacturer") "SHOU HAN(首韩)"))
      (libsource (lib "easyedapro") (part "TS665CJ"))
    )
    (comp (ref "S3")
      (value "TS665CJ")
      (footprint "easyedapro:SW-TH_4P-L6.0-W6.0-P4.50-LS6.5")
      (description "触点电流:50mA;额定电压(DC):12V;电路结构:单刀单掷;安装方式:直插;带灯:-;机械寿命:-;")
      (fields (field (name "Manufacturer") "SHOU HAN(首韩)"))
      (libsource (lib "easyedapro") (part "TS665CJ"))
    )
    (comp (ref "S4")
      (value "TS665CJ")
      (footprint "easyedapro:SW-TH_4P-L6.0-W6.0-P4.50-LS6.5")
      (description "触点电流:50mA;额定电压(DC):12V;电路结构:单刀单掷;安装方式:直插;带灯:-;机械寿命:-;")
      (fields (field (name "Manufacturer") "SHOU HAN(首韩)"))
      (libsource (lib "easyedapro") (part "TS665CJ"))
    )
    (comp (ref "S5")
      (value "TS665CJ")
      (footprint "easyedapro:SW-TH_4P-L6.0-W6.0-P4.50-LS6.5")
      (description "触点电流:50mA;额定电压(DC):12V;电路结构:单刀单掷;安装方式:直插;带灯:-;机械寿命:-;")
      (fields (field (name "Manufacturer") "SHOU HAN(首韩)"))
      (libsource (lib "easyedapro") (part "TS665CJ"))
    )
    (comp (ref "S6")
      (value "TS665CJ")
      (footprint "easyedapro:SW-TH_4P-L6.0-W6.0-P4.50-LS6.5")
      (description "触点电流:50mA;额定电压(DC):12V;电路结构:单刀单掷;安装方式:直插;带灯:-;机械寿命:-;")
      (fields (field (name "Manufacturer") "SHOU HAN(首韩)"))
      (libsource (lib "easyedapro") (part "TS665CJ"))
    )
    (comp (ref "S7")
      (value "PS-5850A-6PL")
      (footprint "easyedapro:SW-TH_6P-L5.8-W5.8-P2.00-LS4.5-BL")
      (description "5.8自锁按键开关 高头 耐高温")
      (fields (field (name "Manufacturer") "G-Switch(品赞)"))
      (libsource (lib "easyedapro") (part "PS-5850A-6PL"))
    )
    (comp (ref "T1")
      (value "~")
      (footprint "easyedapro:HDR-TH_1P-V-M_XKB_X4611WV-01I-C28D40")
      (libsource (lib "easyedapro") (part "HDR_1x1"))
    )
    (comp (ref "T2")
      (value "~")
      (footprint "easyedapro:HDR-TH_1P-V-M_XKB_X4611WV-01I-C28D40")
      (libsource (lib "easyedapro") (part "HDR_1x1"))
    )
    (comp (ref "T3")
      (value "~")
      (footprint "easyedapro:HDR-TH_1P-V-M_XKB_X4611WV-01I-C28D40")
      (libsource (lib "easyedapro") (part "HDR_1x1"))
    )
    (comp (ref "T4")
      (value "~")
      (footprint "easyedapro:HDR-TH_1P-V-M_XKB_X4611WV-01I-C28D40")
      (libsource (lib "easyedapro") (part "HDR_1x1"))
    )
    (comp (ref "T5")
      (value "~")
      (footprint "easyedapro:HDR-TH_1P-V-M_XKB_X4611WV-01I-C28D40")
      (libsource (lib "easyedapro") (part "HDR_1x1"))
    )
    (comp (ref "T6")
      (value "~")
      (footprint "easyedapro:HDR-TH_1P-V-M_XKB_X4611WV-01I-C28D40")
      (libsource (lib "easyedapro") (part "HDR_1x1"))
    )
    (comp (ref "T7")
      (value "~")
      (footprint "easyedapro:HDR-TH_1P-V-M_XKB_X4611WV-01I-C28D40")
      (libsource (lib "easyedapro") (part "HDR_1x1"))
    )
    (comp (ref "T8")
      (value "~")
      (footprint "easyedapro:HDR-TH_1P-V-M_XKB_X4611WV-01I-C28D40")
      (libsource (lib "easyedapro") (part "HDR_1x1"))
    )
    (comp (ref "T9")
      (value "~")
      (footprint "easyedapro:HDR-TH_1P-V-M_XKB_X4611WV-01I-C28D40")
      (libsource (lib "easyedapro") (part "HDR_1x1"))
    )
    (comp (ref "U1")
      (value "STC12C5A32S2-35I-PDIP40")
      (footprint "easyedapro:DIP-40_L52.3-W13.9-P2.54-LS15.2-BL")
      (description "CPU内核:51系列;CPU最大主频:35MHz;程序存储容量:32KB;程序存储器类型:FLASH;RAM总容量:1.25KB;GPIO端口数量:36;")
      (fields (field (name "Manufacturer") "STC(宏晶)"))
      (libsource (lib "easyedapro") (part "STC12C5A32S2"))
    )
    (comp (ref "U2")
      (value "TL431")
      (footprint "easyedapro:TO-92-3_L4.9-W3.7-P1.27-L")
      (description "输出类型:可调;输出电压:2.495V~40V;输出电流:150mA;最小阴极电流调节:500uA;工作温度:-40°C~+125°C@(TA);")
      (fields (field (name "Manufacturer") "HTC"))
      (libsource (lib "easyedapro") (part "TL431C"))
    )
    (comp (ref "U3")
      (value "TL084")
      (footprint "easyedapro:DIP-14_L18.9-W6.4-P2.54-LS7.6-BL")
      (fields (field (name "Manufacturer") "Gcore(扬州国芯)"))
      (libsource (lib "easyedapro") (part "TL084_C5157925"))
    )
    (comp (ref "U4")
      (value "MAX232ESE")
      (footprint "easyedapro:SOP-16_L10.0-W3.9-P1.27-LS6.0-BL")
      (description "类型:收发器;驱动器/接收器:2/2;数据速率:120Kbps;")
      (fields (field (name "Manufacturer") "UMW(广东友台半导体)"))
      (libsource (lib "easyedapro") (part "MAX232ESE_C2904791"))
    )
    (comp (ref "U5")
      (value "TL084")
      (footprint "easyedapro:DIP-14_L18.9-W6.4-P2.54-LS7.6-BL")
      (fields (field (name "Manufacturer") "Gcore(扬州国芯)"))
      (libsource (lib "easyedapro") (part "TL084_C5157925"))
    )
    (comp (ref "U6")
      (value "MC34063A")
      (footprint "easyedapro:SOIC-8_L4.9-W3.9-P1.27-LS6.0-BL")
      (fields (field (name "Manufacturer") "Slkor(萨科微)"))
      (libsource (lib "easyedapro") (part "MC34063A"))
    )
    (comp (ref "U7")
      (value "MC34063A")
      (footprint "easyedapro:SOIC-8_L4.9-W3.9-P1.27-LS6.0-BL")
      (fields (field (name "Manufacturer") "Slkor(萨科微)"))
      (libsource (lib "easyedapro") (part "MC34063A"))
    )
    (comp (ref "U8")
      (value "TLP521")
      (footprint "easyedapro:DIP-4_L6.4-W4.6-P2.54-LS7.6-BL")
      (fields (field (name "Manufacturer") "OCIC(卓睿科)"))
      (libsource (lib "easyedapro") (part "CYTLP521-1(GB)"))
    )
    (comp (ref "U9")
      (value "AMS1117-5.0")
      (footprint "easyedapro:SOT-223_L6.5-W3.5-P2.30-LS7.0-BR")
      (description "输出类型:固定;输出极性:正;最大输入电压:15V;输出电压:5V;输出电流:1A;电源纹波抑制比(PSRR):68dB@(120Hz);")
      (fields (field (name "Manufacturer") "AMS"))
      (libsource (lib "easyedapro") (part "AMS1117-5.0"))
    )
    (comp (ref "VD1")
      (value "1N4148")
      (footprint "easyedapro:DO-35_BD2.0-L4.0-P8.00-D0.5-FD")
      (fields (field (name "Manufacturer") "ST(先科)"))
      (libsource (lib "easyedapro") (part "1N4148"))
    )
    (comp (ref "VD2")
      (value "1N4148")
      (footprint "easyedapro:DO-35_BD2.0-L4.0-P8.00-D0.5-FD")
      (fields (field (name "Manufacturer") "ST(先科)"))
      (libsource (lib "easyedapro") (part "1N4148"))
    )
    (comp (ref "VD3")
      (value "1N4148")
      (footprint "easyedapro:DO-35_BD2.0-L4.0-P8.00-D0.5-FD")
      (fields (field (name "Manufacturer") "ST(先科)"))
      (libsource (lib "easyedapro") (part "1N4148"))
    )
    (comp (ref "VD4")
      (value "1N4148")
      (footprint "easyedapro:DO-35_BD2.0-L4.0-P8.00-D0.5-FD")
      (fields (field (name "Manufacturer") "ST(先科)"))
      (libsource (lib "easyedapro") (part "1N4148"))
    )
    (comp (ref "VD6")
      (value "1N4148")
      (footprint "easyedapro:DO-35_BD2.0-L4.0-P8.00-D0.5-FD")
      (fields (field (name "Manufacturer") "ST(先科)"))
      (libsource (lib "easyedapro") (part "1N4148"))
    )
    (comp (ref "VD7")
      (value "1N4148")
      (footprint "easyedapro:DO-35_BD2.0-L4.0-P8.00-D0.5-FD")
      (fields (field (name "Manufacturer") "ST(先科)"))
      (libsource (lib "easyedapro") (part "1N4148"))
    )
    (comp (ref "VD8")
      (value "1N4007")
      (footprint "easyedapro:SMA_L4.3-W2.5-LS5.0-RD")
      (description "正向压降(Vf):1.1V 1A;反向电流(Ir):5uA 1kV;直流反向耐压(Vr):1kV;二极管配置:独立式;平均整流电流(Io):1A;")
      (fields (field (name "Manufacturer") "TWGMC(台湾迪嘉)"))
      (libsource (lib "easyedapro") (part "1N4007_C727081"))
    )
    (comp (ref "VD9")
      (value "1N4007")
      (footprint "easyedapro:SMA_L4.3-W2.5-LS5.0-RD")
      (description "正向压降(Vf):1.1V 1A;反向电流(Ir):5uA 1kV;直流反向耐压(Vr):1kV;二极管配置:独立式;平均整流电流(Io):1A;")
      (fields (field (name "Manufacturer") "TWGMC(台湾迪嘉)"))
      (libsource (lib "easyedapro") (part "1N4007_C727081"))
    )
    (comp (ref "VD10")
      (value "1N4007")
      (footprint "easyedapro:SMA_L4.3-W2.5-LS5.0-RD")
      (description "正向压降(Vf):1.1V 1A;反向电流(Ir):5uA 1kV;直流反向耐压(Vr):1kV;二极管配置:独立式;平均整流电流(Io):1A;")
      (fields (field (name "Manufacturer") "TWGMC(台湾迪嘉)"))
      (libsource (lib "easyedapro") (part "1N4007_C727081"))
    )
    (comp (ref "VD11")
      (value "1N4007")
      (footprint "easyedapro:SMA_L4.3-W2.5-LS5.0-RD")
      (description "正向压降(Vf):1.1V 1A;反向电流(Ir):5uA 1kV;直流反向耐压(Vr):1kV;二极管配置:独立式;平均整流电流(Io):1A;")
      (fields (field (name "Manufacturer") "TWGMC(台湾迪嘉)"))
      (libsource (lib "easyedapro") (part "1N4007_C727081"))
    )
    (comp (ref "VD12")
      (value "1N4148")
      (footprint "easyedapro:DO-35_BD2.0-L4.0-P8.00-D0.5-FD")
      (fields (field (name "Manufacturer") "ST(先科)"))
      (libsource (lib "easyedapro") (part "1N4148"))
    )
    (comp (ref "VD13")
      (value "1N4148")
      (footprint "easyedapro:DO-35_BD2.0-L4.0-P8.00-D0.5-FD")
      (fields (field (name "Manufacturer") "ST(先科)"))
      (libsource (lib "easyedapro") (part "1N4148"))
    )
    (comp (ref "VD14")
      (value "1N5819W")
      (footprint "easyedapro:SOD-323_L1.8-W1.3-LS2.5-RD")
      (description "直流反向耐压(Vr):40V;平均整流电流(Io):1A;正向压降(Vf):600mV@1A;")
      (fields (field (name "Manufacturer") "TWGMC(台湾迪嘉)"))
      (libsource (lib "easyedapro") (part "1N5819WS"))
    )
    (comp (ref "VD15")
      (value "1N4148")
      (footprint "easyedapro:DO-35_BD2.0-L4.0-P8.00-D0.5-FD")
      (fields (field (name "Manufacturer") "ST(先科)"))
      (libsource (lib "easyedapro") (part "1N4148"))
    )
    (comp (ref "VD16")
      (value "1N5819W")
      (footprint "easyedapro:SOD-323_L1.8-W1.3-LS2.5-RD")
      (description "直流反向耐压(Vr):40V;平均整流电流(Io):1A;正向压降(Vf):600mV@1A;")
      (fields (field (name "Manufacturer") "TWGMC(台湾迪嘉)"))
      (libsource (lib "easyedapro") (part "1N5819WS"))
    )
    (comp (ref "VS1")
      (value "1N4733A")
      (footprint "easyedapro:DO-41_BD2.4-L4.7-P8.70-D0.9-RD")
      (description "二极管配置:独立式;稳压值(标称值):5.1V;稳压值(范围):4.845V~5.355V;功率:1W;精度:±5%;")
      (fields (field (name "Manufacturer") "onsemi(安森美)"))
      (libsource (lib "easyedapro") (part "1N4733A_C140851"))
    )
    (comp (ref "VT1")
      (value "S9012")
      (footprint "easyedapro:SOT-23-3_L2.9-W1.3-P1.90-LS2.4-BR")
      (fields (field (name "Manufacturer") "FUXINSEMI(富芯森美)"))
      (libsource (lib "easyedapro") (part "S9012_C842815"))
    )
    (comp (ref "VT2")
      (value "9012")
      (footprint "easyedapro:SOT-23-3_L2.9-W1.3-P1.90-LS2.4-BR")
      (fields (field (name "Manufacturer") "FUXINSEMI(富芯森美)"))
      (libsource (lib "easyedapro") (part "S9012_C842815"))
    )
    (comp (ref "VT3")
      (value "S9012")
      (footprint "easyedapro:SOT-23-3_L2.9-W1.3-P1.90-LS2.4-BR")
      (fields (field (name "Manufacturer") "FUXINSEMI(富芯森美)"))
      (libsource (lib "easyedapro") (part "S9012_C842815"))
    )
    (comp (ref "VT4")
      (value "9012")
      (footprint "easyedapro:SOT-23-3_L2.9-W1.3-P1.90-LS2.4-BR")
      (fields (field (name "Manufacturer") "FUXINSEMI(富芯森美)"))
      (libsource (lib "easyedapro") (part "S9012_C842815"))
    )
    (comp (ref "VT5")
      (value "9012")
      (footprint "easyedapro:SOT-23-3_L2.9-W1.3-P1.90-LS2.4-BR")
      (fields (field (name "Manufacturer") "FUXINSEMI(富芯森美)"))
      (libsource (lib "easyedapro") (part "S9012_C842815"))
    )
    (comp (ref "VT6")
      (value "9012")
      (footprint "easyedapro:SOT-23-3_L2.9-W1.3-P1.90-LS2.4-BR")
      (fields (field (name "Manufacturer") "FUXINSEMI(富芯森美)"))
      (libsource (lib "easyedapro") (part "S9012_C842815"))
    )
    (comp (ref "Y1")
      (value "11.0592MHz")
      (footprint "easyedapro:HC-49US_L11.5-W4.5-P4.88")
      (description "频率:11.0592MHz;频率公差:±20ppm;频率稳定度:±30ppm;负载电容:20pF;")
      (fields
        (field (name "Manufacturer Part") "X49SD110592MSD2SC")
        (field (name "Manufacturer") "YXC(扬兴晶振)")
      )
      (libsource (lib "easyedapro") (part "X49SD110592MSD2SC"))
    )
  )
  (nets
    (net (code "1") (name "+12V") (class "Default")
      (node (ref "C18") (pin "2") (pinfunction "2_2") (pintype "input"))
      (node (ref "C20") (pin "2") (pinfunction "2_2") (pintype "input"))
      (node (ref "C22") (pin "1") (pinfunction "1_1") (pintype "input"))
      (node (ref "L2") (pin "2") (pinfunction "2_2") (pintype "input"))
      (node (ref "R50") (pin "1") (pinfunction "1_1") (pintype "input"))
      (node (ref "R53") (pin "1") (pinfunction "1_1") (pintype "input"))
      (node (ref "T2") (pin "1") (pinfunction "1_1") (pintype "unspecified"))
      (node (ref "U3") (pin "4") (pinfunction "V+_4") (pintype "input"))
      (node (ref "U5") (pin "4") (pinfunction "V+_4") (pintype "input"))
    )
    (net (code "2") (name "-12V") (class "Default")
      (node (ref "C19") (pin "2") (pinfunction "2_2") (pintype "input"))
      (node (ref "C21") (pin "2") (pinfunction "2_2") (pintype "input"))
      (node (ref "C31") (pin "2") (pinfunction "2_2") (pintype "input"))
      (node (ref "L4") (pin "2") (pinfunction "2_2") (pintype "input"))
      (node (ref "T3") (pin "1") (pinfunction "1_1") (pintype "unspecified"))
      (node (ref "U3") (pin "11") (pinfunction "V-_11") (pintype "input"))
      (node (ref "U5") (pin "11") (pinfunction "V-_11") (pintype "input"))
    )
    (net (code "3") (name "/DY") (class "Default")
      (node (ref "K1") (pin "5") (pinfunction "5_5") (pintype "input"))
      (node (ref "K2") (pin "5") (pinfunction "5_5") (pintype "input"))
      (node (ref "K3") (pin "5") (pinfunction "5_5") (pintype "input"))
      (node (ref "K4") (pin "5") (pinfunction "5_5") (pintype "input"))
      (node (ref "R21") (pin "1") (pinfunction "1_1") (pintype "input"))
      (node (ref "R33") (pin "1") (pinfunction "1_1") (pintype "input"))
      (node (ref "U3") (pin "8") (pinfunction "OUT_8") (pintype "output"))
    )
    (net (code "4") (name "/HS") (class "Default")
      (node (ref "J2") (pin "1") (pinfunction "1_1") (pintype "unspecified"))
      (node (ref "P1") (pin "3") (pinfunction "3_3") (pintype "input"))
      (node (ref "R12") (pin "1") (pinfunction "1_1") (pintype "input"))
      (node (ref "R13") (pin "1") (pinfunction "1_1") (pintype "input"))
      (node (ref "R14") (pin "1") (pinfunction "1_1") (pintype "input"))
      (node (ref "R15") (pin "1") (pinfunction "1_1") (pintype "input"))
      (node (ref "R22") (pin "2") (pinfunction "2_2") (pintype "input"))
      (node (ref "U3") (pin "9") (pinfunction "IN-_9") (pintype "input"))
      (node (ref "VD10") (pin "1") (pinfunction "K_1") (pintype "input"))
      (node (ref "VD11") (pin "2") (pinfunction "A_2") (pintype "input"))
    )
    (net (code "5") (name "/LEDA") (class "Default")
      (node (ref "LCD1") (pin "15") (pinfunction "A_15") (pintype "input"))
      (node (ref "R57") (pin "1") (pinfunction "1_1") (pintype "input"))
    )
    (net (code "6") (name "/P0.0") (class "Default")
      (node (ref "LCD1") (pin "7") (pinfunction "DB0_7") (pintype "input"))
      (node (ref "RN1") (pin "9") (pinfunction "9_9") (pintype "input"))
      (node (ref "U1") (pin "39") (pinfunction "P0.0_39") (pintype "input"))
    )
    (net (code "7") (name "/P0.1") (class "Default")
      (node (ref "LCD1") (pin "8") (pinfunction "DB1_8") (pintype "input"))
      (node (ref "RN1") (pin "8") (pinfunction "8_8") (pintype "input"))
      (node (ref "U1") (pin "38") (pinfunction "P0.1_38") (pintype "input"))
    )
    (net (code "8") (name "/P0.2") (class "Default")
      (node (ref "LCD1") (pin "9") (pinfunction "DB2_9") (pintype "input"))
      (node (ref "RN1") (pin "7") (pinfunction "7_7") (pintype "input"))
      (node (ref "U1") (pin "37") (pinfunction "P0.2_37") (pintype "input"))
    )
    (net (code "9") (name "/P0.3") (class "Default")
      (node (ref "LCD1") (pin "10") (pinfunction "DB3_10") (pintype "input"))
      (node (ref "RN1") (pin "6") (pinfunction "6_6") (pintype "input"))
      (node (ref "U1") (pin "36") (pinfunction "P0.3_36") (pintype "input"))
    )
    (net (code "10") (name "/P0.4") (class "Default")
      (node (ref "LCD1") (pin "11") (pinfunction "DB4_11") (pintype "input"))
      (node (ref "RN1") (pin "5") (pinfunction "5_5") (pintype "input"))
      (node (ref "U1") (pin "35") (pinfunction "P0.4_35") (pintype "input"))
    )
    (net (code "11") (name "/P0.5") (class "Default")
      (node (ref "LCD1") (pin "12") (pinfunction "DB5_12") (pintype "input"))
      (node (ref "RN1") (pin "4") (pinfunction "4_4") (pintype "input"))
      (node (ref "U1") (pin "34") (pinfunction "P0.5_34") (pintype "input"))
    )
    (net (code "12") (name "/P0.6") (class "Default")
      (node (ref "LCD1") (pin "13") (pinfunction "DB6_13") (pintype "input"))
      (node (ref "RN1") (pin "3") (pinfunction "3_3") (pintype "input"))
      (node (ref "U1") (pin "33") (pinfunction "P0.6_33") (pintype "input"))
    )
    (net (code "13") (name "/P0.7") (class "Default")
      (node (ref "LCD1") (pin "14") (pinfunction "DB7_14") (pintype "input"))
      (node (ref "RN1") (pin "2") (pinfunction "2_2") (pintype "input"))
      (node (ref "U1") (pin "32") (pinfunction "P0.7_32") (pintype "input"))
    )
    (net (code "14") (name "/P1.0") (class "Default")
      (node (ref "C17") (pin "2") (pinfunction "2_2") (pintype "input"))
      (node (ref "R42") (pin "2") (pinfunction "2_2") (pintype "input"))
      (node (ref "R46") (pin "1") (pinfunction "1_1") (pintype "input"))
      (node (ref "T7") (pin "1") (pinfunction "1_1") (pintype "unspecified"))
      (node (ref "U1") (pin "1") (pinfunction "CLKOUT2/ADC0/P1.0_1") (pintype "input"))
      (node (ref "VD15") (pin "1") (pinfunction "C_1") (pintype "input"))
      (node (ref "VS1") (pin "1") (pinfunction "C_1") (pintype "unspecified"))
    )
    (net (code "15") (name "/P1.1") (class "Default")
      (node (ref "R10") (pin "2") (pinfunction "2_2") (pintype "input"))
      (node (ref "U1") (pin "2") (pinfunction "ACD1/P1.1_2") (pintype "input"))
      (node (ref "U2") (pin "1") (pinfunction "R_1") (pintype "input"))
      (node (ref "U2") (pin "3") (pinfunction "C_3") (pintype "input"))
    )
    (net (code "16") (name "/P1.2") (class "Default")
      (node (ref "S1") (pin "2") (pinfunction "B_2") (pintype "input"))
      (node (ref "U1") (pin "3") (pinfunction "RXD2/ECI/ADC2/P1.2_3") (pintype "input"))
    )
    (net (code "17") (name "/P1.3") (class "Default")
      (node (ref "S2") (pin "2") (pinfunction "B_2") (pintype "input"))
      (node (ref "U1") (pin "4") (pinfunction "TXD2/CPP0/ADC3/P1.3_4") (pintype "input"))
    )
    (net (code "18") (name "/P1.4") (class "Default")
      (node (ref "S3") (pin "2") (pinfunction "B_2") (pintype "input"))
      (node (ref "U1") (pin "5") (pinfunction "SS/CPP1/ADC4/P1.4_5") (pintype "input"))
    )
    (net (code "19") (name "/P1.5") (class "Default")
      (node (ref "S4") (pin "2") (pinfunction "B_2") (pintype "input"))
      (node (ref "U1") (pin "6") (pinfunction "MOSI/ADC5/P1.5_6") (pintype "input"))
    )
    (net (code "20") (name "/P1.6") (class "Default")
      (node (ref "S5") (pin "2") (pinfunction "B_2") (pintype "input"))
      (node (ref "U1") (pin "7") (pinfunction "MISO/ADC6/P1.6_7") (pintype "input"))
    )
    (net (code "21") (name "/P1.7") (class "Default")
      (node (ref "R16") (pin "2") (pinfunction "2_2") (pintype "input"))
      (node (ref "R18") (pin "1") (pinfunction "1_1") (pintype "input"))
      (node (ref "U1") (pin "31") (pinfunction "EX_LVD/P4.6/RST2_31") (pintype "input"))
      (node (ref "U1") (pin "8") (pinfunction "SCLK/ADC7/P1.7_8") (pintype "input"))
    )
    (net (code "22") (name "/P2.3") (class "Default")
      (node (ref "R26") (pin "2") (pinfunction "2_2") (pintype "input"))
      (node (ref "R29") (pin "2") (pinfunction "2_2") (pintype "input"))
      (node (ref "U1") (pin "24") (pinfunction "P2.3/A11_24") (pintype "input"))
    )
    (net (code "23") (name "/P2.4") (class "Default")
      (node (ref "R27") (pin "2") (pinfunction "2_2") (pintype "input"))
      (node (ref "R30") (pin "2") (pinfunction "2_2") (pintype "input"))
      (node (ref "U1") (pin "25") (pinfunction "P2.4/A12_25") (pintype "input"))
    )
    (net (code "24") (name "/P2.5") (class "Default")
      (node (ref "LCD1") (pin "6") (pinfunction "E_6") (pintype "input"))
      (node (ref "U1") (pin "26") (pinfunction "P2.5/A13_26") (pintype "input"))
    )
    (net (code "25") (name "/P2.6") (class "Default")
      (node (ref "LCD1") (pin "5") (pinfunction "RW_5") (pintype "input"))
      (node (ref "U1") (pin "27") (pinfunction "P2.6/A14_27") (pintype "input"))
    )
    (net (code "26") (name "/P2.7") (class "Default")
      (node (ref "LCD1") (pin "4") (pinfunction "RS_4") (pintype "input"))
      (node (ref "U1") (pin "28") (pinfunction "P2.7/A15_28") (pintype "input"))
    )
    (net (code "27") (name "/P3.0") (class "Default")
      (node (ref "U1") (pin "10") (pinfunction "INT#/RXD/P3.0_10") (pintype "input"))
      (node (ref "U4") (pin "12") (pinfunction "R1OUT_12") (pintype "input"))
    )
    (net (code "28") (name "/P3.1") (class "Default")
      (node (ref "U1") (pin "11") (pinfunction "TXD/P3.1_11") (pintype "input"))
      (node (ref "U4") (pin "11") (pinfunction "T1IN_11") (pintype "input"))
    )
    (net (code "29") (name "/P3.2") (class "Default")
      (node (ref "R51") (pin "2") (pinfunction "2_2") (pintype "input"))
      (node (ref "U1") (pin "12") (pinfunction "INT0#/P3.2_12") (pintype "input"))
      (node (ref "U8") (pin "4") (pinfunction "COL_4") (pintype "input"))
    )
    (net (code "30") (name "/P3.3") (class "Default")
      (node (ref "S6") (pin "2") (pinfunction "B_2") (pintype "input"))
      (node (ref "U1") (pin "13") (pinfunction "INT1#/P3.3_13") (pintype "input"))
    )
    (net (code "31") (name "/P3.4") (class "Default")
      (node (ref "R5") (pin "1") (pinfunction "1_1") (pintype "input"))
      (node (ref "R9") (pin "1") (pinfunction "1_1") (pintype "input"))
      (node (ref "U1") (pin "14") (pinfunction "CLKOUT0/INT#/T0/P3.4_14") (pintype "input"))
    )
    (net (code "32") (name "/P3.5") (class "Default")
      (node (ref "R4") (pin "1") (pinfunction "1_1") (pintype "input"))
      (node (ref "R8") (pin "1") (pinfunction "1_1") (pintype "input"))
      (node (ref "U1") (pin "15") (pinfunction "CLKOUT1/INT#/T1/P3.5_15") (pintype "input"))
    )
    (net (code "33") (name "/P3.6") (class "Default")
      (node (ref "R3") (pin "1") (pinfunction "1_1") (pintype "input"))
      (node (ref "R7") (pin "1") (pinfunction "1_1") (pintype "input"))
      (node (ref "U1") (pin "16") (pinfunction "WR#/P3.6_16") (pintype "input"))
    )
    (net (code "34") (name "/P3.7") (class "Default")
      (node (ref "R2") (pin "1") (pinfunction "1_1") (pintype "input"))
      (node (ref "R6") (pin "1") (pinfunction "1_1") (pintype "input"))
      (node (ref "U1") (pin "17") (pinfunction "RD#/P3.7_17") (pintype "input"))
    )
    (net (code "35") (name "/RST") (class "Default")
      (node (ref "C2") (pin "2") (pinfunction "2_2") (pintype "input"))
      (node (ref "D5") (pin "1") (pinfunction "C_1") (pintype "input"))
      (node (ref "R11") (pin "2") (pinfunction "2_2") (pintype "input"))
      (node (ref "U1") (pin "9") (pinfunction "P4.7/RST_9") (pintype "input"))
    )
    (net (code "36") (name "/V0") (class "Default")
      (node (ref "LCD1") (pin "3") (pinfunction "V0_3") (pintype "input"))
      (node (ref "RP1") (pin "2") (pinfunction "2_2") (pintype "input"))
    )
    (net (code "37") (name "AGND") (class "Default")
      (node (ref "C18") (pin "1") (pinfunction "1_1") (pintype "input"))
      (node (ref "C19") (pin "1") (pinfunction "1_1") (pintype "input"))
      (node (ref "C20") (pin "1") (pinfunction "1_1") (pintype "input"))
      (node (ref "C21") (pin "1") (pinfunction "1_1") (pintype "input"))
      (node (ref "C22") (pin "2") (pinfunction "2_2") (pintype "input"))
      (node (ref "C23") (pin "2") (pinfunction "2_2") (pintype "input"))
      (node (ref "C24") (pin "2") (pinfunction "2_2") (pintype "input"))
      (node (ref "C25") (pin "2") (pinfunction "2_2") (pintype "input"))
      (node (ref "C26") (pin "1") (pinfunction "1_1") (pintype "input"))
      (node (ref "C27") (pin "2") (pinfunction "2_2") (pintype "input"))
      (node (ref "C28") (pin "1") (pinfunction "1_1") (pintype "input"))
      (node (ref "C30") (pin "1") (pinfunction "1_1") (pintype "input"))
      (node (ref "C31") (pin "1") (pinfunction "1_1") (pintype "input"))
      (node (ref "C8") (pin "1") (pinfunction "1_1") (pintype "input"))
      (node (ref "L3") (pin "2") (pinfunction "2_2") (pintype "input"))
      (node (ref "P2") (pin "1") (pinfunction "1_1") (pintype "input"))
      (node (ref "R20") (pin "1") (pinfunction "1_1") (pintype "input"))
      (node (ref "R28") (pin "1") (pinfunction "1_1") (pintype "input"))
      (node (ref "R34") (pin "1") (pinfunction "1_1") (pintype "input"))
      (node (ref "R37") (pin "2") (pinfunction "2_2") (pintype "input"))
      (node (ref "R47") (pin "1") (pinfunction "1_1") (pintype "input"))
      (node (ref "R48") (pin "1") (pinfunction "1_1") (pintype "input"))
      (node (ref "R49") (pin "1") (pinfunction "1_1") (pintype "input"))
      (node (ref "R54") (pin "2") (pinfunction "2_2") (pintype "input"))
      (node (ref "R56") (pin "2") (pinfunction "2_2") (pintype "input"))
      (node (ref "T8") (pin "1") (pinfunction "1_1") (pintype "unspecified"))
      (node (ref "U3") (pin "10") (pinfunction "IN+_10") (pintype "input"))
      (node (ref "U3") (pin "12") (pinfunction "IN+_12") (pintype "input"))
      (node (ref "U3") (pin "5") (pinfunction "IN+_5") (pintype "input"))
      (node (ref "U6") (pin "2") (pinfunction "SWE_2") (pintype "input"))
      (node (ref "U6") (pin "4") (pinfunction "GND_4") (pintype "input"))
      (node (ref "VD10") (pin "2") (pinfunction "A_2") (pintype "input"))
      (node (ref "VD11") (pin "1") (pinfunction "K_1") (pintype "input"))
      (node (ref "VD15") (pin "2") (pinfunction "A_2") (pintype "input"))
      (node (ref "VD8") (pin "2") (pinfunction "A_2") (pintype "input"))
      (node (ref "VD9") (pin "1") (pinfunction "K_1") (pintype "input"))
      (node (ref "VS1") (pin "2") (pinfunction "A_2") (pintype "unspecified"))
    )
    (net (code "38") (name "DGND") (class "Default")
      (node (ref "C1") (pin "1") (pinfunction "1_1") (pintype "input"))
      (node (ref "C11") (pin "1") (pinfunction "1_1") (pintype "input"))
      (node (ref "C12") (pin "2") (pinfunction "2_2") (pintype "input"))
      (node (ref "C16") (pin "1") (pinfunction "1_1") (pintype "input"))
      (node (ref "C3") (pin "1") (pinfunction "1_1") (pintype "input"))
      (node (ref "C32") (pin "2") (pinfunction "2_2") (pintype "input"))
      (node (ref "C33") (pin "2") (pinfunction "2_2") (pintype "input"))
      (node (ref "C4") (pin "2") (pinfunction "2_2") (pintype "input"))
      (node (ref "C5") (pin "1") (pinfunction "1_1") (pintype "input"))
      (node (ref "C6") (pin "1") (pinfunction "1_1") (pintype "input"))
      (node (ref "D5") (pin "2") (pinfunction "A_2") (pintype "input"))
      (node (ref "J3") (pin "5") (pinfunction "5_5") (pintype "input"))
      (node (ref "K1") (pin "3") (pinfunction "3_3") (pintype "input"))
      (node (ref "K2") (pin "3") (pinfunction "3_3") (pintype "input"))
      (node (ref "K3") (pin "3") (pinfunction "3_3") (pintype "input"))
      (node (ref "K4") (pin "3") (pinfunction "3_3") (pintype "input"))
      (node (ref "LCD1") (pin "1") (pinfunction "VSS_1") (pintype "input"))
      (node (ref "LCD1") (pin "16") (pinfunction "K_16") (pintype "input"))
      (node (ref "LS1") (pin "2") (pinfunction "2_2") (pintype "input"))
      (node (ref "R11") (pin "1") (pinfunction "1_1") (pintype "input"))
      (node (ref "R18") (pin "2") (pinfunction "2_2") (pintype "input"))
      (node (ref "R49") (pin "2") (pinfunction "2_2") (pintype "input"))
      (node (ref "RP1") (pin "1") (pinfunction "1_1") (pintype "input"))
      (node (ref "S1") (pin "3") (pinfunction "C_3") (pintype "input"))
      (node (ref "S2") (pin "3") (pinfunction "C_3") (pintype "input"))
      (node (ref "S3") (pin "3") (pinfunction "C_3") (pintype "input"))
      (node (ref "S4") (pin "3") (pinfunction "C_3") (pintype "input"))
      (node (ref "S5") (pin "3") (pinfunction "C_3") (pintype "input"))
      (node (ref "S6") (pin "3") (pinfunction "C_3") (pintype "input"))
      (node (ref "U1") (pin "20") (pinfunction "GND_20") (pintype "input"))
      (node (ref "U2") (pin "2") (pinfunction "A_2") (pintype "input"))
      (node (ref "U4") (pin "15") (pinfunction "GND_15") (pintype "input"))
      (node (ref "U8") (pin "3") (pinfunction "EMI_3") (pintype "input"))
      (node (ref "U9") (pin "1") (pinfunction "GND_1") (pintype "input"))
      (node (ref "VD1") (pin "2") (pinfunction "A_2") (pintype "input"))
      (node (ref "VD2") (pin "2") (pinfunction "A_2") (pintype "input"))
      (node (ref "VD3") (pin "2") (pinfunction "A_2") (pintype "input"))
      (node (ref "VD4") (pin "2") (pinfunction "A_2") (pintype "input"))
    )
    (net (code "39") (name "Net-(C7-Pad1)") (class "Default")
      (node (ref "C7") (pin "1") (pinfunction "1_1") (pintype "input"))
      (node (ref "R25") (pin "2") (pinfunction "2_2") (pintype "input"))
    )
    (net (code "40") (name "Net-(C14-Pad1)") (class "Default")
      (node (ref "C14") (pin "1") (pinfunction "1_1") (pintype "input"))
      (node (ref "C15") (pin "1") (pinfunction "1_1") (pintype "input"))
      (node (ref "R33") (pin "2") (pinfunction "2_2") (pintype "input"))
      (node (ref "R37") (pin "1") (pinfunction "1_1") (pintype "input"))
    )
    (net (code "41") (name "Net-(C17-Pad1)") (class "Default")
      (node (ref "C17") (pin "1") (pinfunction "1_1") (pintype "input"))
      (node (ref "R40") (pin "1") (pinfunction "1_1") (pintype "input"))
      (node (ref "R44") (pin "2") (pinfunction "2_2") (pintype "input"))
    )
    (net (code "42") (name "Net-(F1-Pad1)") (class "Default")
      (node (ref "F1") (pin "1") (pinfunction "1_1") (pintype "input"))
      (node (ref "S7") (pin "1") (pinfunction "1_1") (pintype "input"))
    )
    (net (code "43") (name "Net-(K1-Pad1)") (class "Default")
      (node (ref "K1") (pin "1") (pinfunction "1_1") (pintype "input"))
      (node (ref "R12") (pin "2") (pinfunction "2_2") (pintype "input"))
    )
    (net (code "44") (name "Net-(K2-Pad1)") (class "Default")
      (node (ref "K2") (pin "1") (pinfunction "1_1") (pintype "input"))
      (node (ref "R13") (pin "2") (pinfunction "2_2") (pintype "input"))
    )
    (net (code "45") (name "Net-(K3-Pad1)") (class "Default")
      (node (ref "K3") (pin "1") (pinfunction "1_1") (pintype "input"))
      (node (ref "R14") (pin "2") (pinfunction "2_2") (pintype "input"))
    )
    (net (code "46") (name "Net-(K4-Pad1)") (class "Default")
      (node (ref "K4") (pin "1") (pinfunction "1_1") (pintype "input"))
      (node (ref "R15") (pin "2") (pinfunction "2_2") (pintype "input"))
    )
    (net (code "47") (name "Net-(LED1-A)") (class "Default")
      (node (ref "LED1") (pin "1") (pinfunction "A_1") (pintype "input"))
      (node (ref "R23") (pin "2") (pinfunction "2_2") (pintype "input"))
    )
    (net (code "48") (name "Net-(LED1-K)") (class "Default")
      (node (ref "LED1") (pin "2") (pinfunction "K_2") (pintype "input"))
      (node (ref "U1") (pin "23") (pinfunction "P2.2/A10_23") (pintype "input"))
    )
    (net (code "49") (name "Net-(LS1-+)") (class "Default")
      (node (ref "LS1") (pin "1") (pinfunction "+_1") (pintype "input"))
      (node (ref "VT5") (pin "3") (pinfunction "C_3") (pintype "input"))
    )
    (net (code "50") (name "Net-(P2-Pad2)") (class "Default")
      (node (ref "P2") (pin "2") (pinfunction "2_2") (pintype "input"))
      (node (ref "S7") (pin "2") (pinfunction "2_2") (pintype "input"))
    )
    (net (code "51") (name "Net-(R19-Pad2)") (class "Default")
      (node (ref "R19") (pin "2") (pinfunction "2_2") (pintype "input"))
      (node (ref "RP3") (pin "1") (pinfunction "1_1") (pintype "input"))
    )
    (net (code "52") (name "Net-(R21-Pad2)") (class "Default")
      (node (ref "R21") (pin "2") (pinfunction "2_2") (pintype "input"))
      (node (ref "R22") (pin "1") (pinfunction "1_1") (pintype "input"))
    )
    (net (code "53") (name "Net-(U1-XTAL1)") (class "Default")
      (node (ref "C6") (pin "2") (pinfunction "2_2") (pintype "input"))
      (node (ref "U1") (pin "19") (pinfunction "XTAL1_19") (pintype "input"))
      (node (ref "Y1") (pin "1") (pinfunction "OSC1_1") (pintype "input"))
    )
    (net (code "54") (name "Net-(U1-XTAL2)") (class "Default")
      (node (ref "C5") (pin "2") (pinfunction "2_2") (pintype "input"))
      (node (ref "U1") (pin "18") (pinfunction "XTAL2_18") (pintype "input"))
      (node (ref "Y1") (pin "2") (pinfunction "OSC2_2") (pintype "input"))
    )
    (net (code "55") (name "Net-(U3A-IN+)") (class "Default")
      (node (ref "C8") (pin "2") (pinfunction "2_2") (pintype "input"))
      (node (ref "R25") (pin "1") (pinfunction "1_1") (pintype "input"))
      (node (ref "R28") (pin "2") (pinfunction "2_2") (pintype "input"))
      (node (ref "U3") (pin "3") (pinfunction "IN+_3") (pintype "input"))
    )
    (net (code "56") (name "Net-(U3A-IN-)") (class "Default")
      (node (ref "R20") (pin "2") (pinfunction "2_2") (pintype "input"))
      (node (ref "RP2") (pin "2") (pinfunction "2_2") (pintype "input"))
      (node (ref "RP2") (pin "3") (pinfunction "3_3") (pintype "input"))
      (node (ref "U3") (pin "2") (pinfunction "IN-_2") (pintype "input"))
    )
    (net (code "57") (name "Net-(U3A-OUT)") (class "Default")
      (node (ref "C7") (pin "2") (pinfunction "2_2") (pintype "input"))
      (node (ref "R17") (pin "2") (pinfunction "2_2") (pintype "input"))
      (node (ref "R24") (pin "2") (pinfunction "2_2") (pintype "input"))
      (node (ref "T4") (pin "1") (pinfunction "1_1") (pintype "unspecified"))
      (node (ref "U3") (pin "1") (pinfunction "OUT_1") (pintype "output"))
      (node (ref "VD6") (pin "2") (pinfunction "A_2") (pintype "input"))
      (node (ref "VD7") (pin "1") (pinfunction "C_1") (pintype "input"))
    )
    (net (code "58") (name "Net-(U3B-IN-)") (class "Default")
      (node (ref "R24") (pin "1") (pinfunction "1_1") (pintype "input"))
      (node (ref "RP3") (pin "2") (pinfunction "2_2") (pintype "input"))
      (node (ref "RP3") (pin "3") (pinfunction "3_3") (pintype "input"))
      (node (ref "U3") (pin "6") (pinfunction "IN-_6") (pintype "input"))
    )
    (net (code "59") (name "Net-(U3B-OUT)") (class "Default")
      (node (ref "J1") (pin "1") (pinfunction "1_1") (pintype "unspecified"))
      (node (ref "P1") (pin "1") (pinfunction "1_1") (pintype "input"))
      (node (ref "R19") (pin "1") (pinfunction "1_1") (pintype "input"))
      (node (ref "T5") (pin "1") (pinfunction "1_1") (pintype "unspecified"))
      (node (ref "U3") (pin "7") (pinfunction "OUT_7") (pintype "output"))
      (node (ref "VD8") (pin "1") (pinfunction "K_1") (pintype "input"))
      (node (ref "VD9") (pin "2") (pinfunction "A_2") (pintype "input"))
    )
    (net (code "60") (name "Net-(U3D-IN-)") (class "Default")
      (node (ref "C14") (pin "2") (pinfunction "2_2") (pintype "input"))
      (node (ref "R35") (pin "1") (pinfunction "1_1") (pintype "input"))
      (node (ref "U3") (pin "13") (pinfunction "IN-_13") (pintype "input"))
    )
    (net (code "61") (name "Net-(U3D-OUT)") (class "Default")
      (node (ref "C15") (pin "2") (pinfunction "2_2") (pintype "input"))
      (node (ref "R35") (pin "2") (pinfunction "2_2") (pintype "input"))
      (node (ref "R38") (pin "2") (pinfunction "2_2") (pintype "input"))
      (node (ref "R39") (pin "2") (pinfunction "2_2") (pintype "input"))
      (node (ref "T6") (pin "1") (pinfunction "1_1") (pintype "unspecified"))
      (node (ref "U3") (pin "14") (pinfunction "OUT_14") (pintype "output"))
      (node (ref "U5") (pin "13") (pinfunction "IN-_13") (pintype "input"))
    )
    (net (code "62") (name "Net-(U4-C1+)") (class "Default")
      (node (ref "C9") (pin "1") (pinfunction "1_1") (pintype "input"))
      (node (ref "U4") (pin "1") (pinfunction "C1+_1") (pintype "input"))
    )
    (net (code "63") (name "Net-(U4-C1-)") (class "Default")
      (node (ref "C9") (pin "2") (pinfunction "2_2") (pintype "input"))
      (node (ref "U4") (pin "3") (pinfunction "C1-_3") (pintype "input"))
    )
    (net (code "64") (name "Net-(U4-C2+)") (class "Default")
      (node (ref "C13") (pin "1") (pinfunction "1_1") (pintype "input"))
      (node (ref "U4") (pin "4") (pinfunction "C2+_4") (pintype "input"))
    )
    (net (code "65") (name "Net-(U4-C2-)") (class "Default")
      (node (ref "C13") (pin "2") (pinfunction "2_2") (pintype "input"))
      (node (ref "U4") (pin "5") (pinfunction "C2-_5") (pintype "input"))
    )
    (net (code "66") (name "Net-(U4-R1IN)") (class "Default")
      (node (ref "J3") (pin "3") (pinfunction "3_3") (pintype "input"))
      (node (ref "U4") (pin "13") (pinfunction "R1IN_13") (pintype "input"))
    )
    (net (code "67") (name "Net-(U4-T1OUT)") (class "Default")
      (node (ref "J3") (pin "2") (pinfunction "2_2") (pintype "input"))
      (node (ref "U4") (pin "14") (pinfunction "T1OUT_14") (pintype "input"))
    )
    (net (code "68") (name "Net-(U4-V+)") (class "Default")
      (node (ref "C10") (pin "1") (pinfunction "1_1") (pintype "input"))
      (node (ref "U4") (pin "2") (pinfunction "V+_2") (pintype "input"))
    )
    (net (code "69") (name "Net-(U4-V-)") (class "Default")
      (node (ref "C16") (pin "2") (pinfunction "2_2") (pintype "input"))
      (node (ref "U4") (pin "6") (pinfunction "V-_6") (pintype "input"))
    )
    (net (code "70") (name "Net-(U5A-IN+)") (class "Default")
      (node (ref "R38") (pin "1") (pinfunction "1_1") (pintype "input"))
      (node (ref "U5") (pin "3") (pinfunction "IN+_3") (pintype "input"))
    )
    (net (code "71") (name "Net-(U5A-IN-)") (class "Default")
      (node (ref "R31") (pin "2") (pinfunction "2_2") (pintype "input"))
      (node (ref "R34") (pin "2") (pinfunction "2_2") (pintype "input"))
      (node (ref "U5") (pin "2") (pinfunction "IN-_2") (pintype "input"))
      (node (ref "VD12") (pin "1") (pinfunction "C_1") (pintype "input"))
    )
    (net (code "72") (name "Net-(U5A-OUT)") (class "Default")
      (node (ref "U5") (pin "1") (pinfunction "OUT_1") (pintype "output"))
      (node (ref "VD12") (pin "2") (pinfunction "A_2") (pintype "input"))
      (node (ref "VD13") (pin "1") (pinfunction "C_1") (pintype "input"))
    )
    (net (code "73") (name "Net-(U5B-IN+)") (class "Default")
      (node (ref "R39") (pin "1") (pinfunction "1_1") (pintype "input"))
      (node (ref "U5") (pin "5") (pinfunction "IN+_5") (pintype "input"))
    )
    (net (code "74") (name "Net-(U5B-IN-)") (class "Default")
      (node (ref "R32") (pin "1") (pinfunction "1_1") (pintype "input"))
      (node (ref "R36") (pin "2") (pinfunction "2_2") (pintype "input"))
      (node (ref "U5") (pin "6") (pinfunction "IN-_6") (pintype "input"))
    )
    (net (code "75") (name "Net-(U5B-OUT)") (class "Default")
      (node (ref "R32") (pin "2") (pinfunction "2_2") (pintype "input"))
      (node (ref "R40") (pin "2") (pinfunction "2_2") (pintype "input"))
      (node (ref "T9") (pin "1") (pinfunction "1_1") (pintype "unspecified"))
      (node (ref "U5") (pin "7") (pinfunction "OUT_7") (pintype "output"))
    )
    (net (code "76") (name "Net-(U5C-IN+)") (class "Default")
      (node (ref "C23") (pin "1") (pinfunction "1_1") (pintype "input"))
      (node (ref "R44") (pin "1") (pinfunction "1_1") (pintype "input"))
      (node (ref "U5") (pin "10") (pinfunction "IN+_10") (pintype "input"))
    )
    (net (code "77") (name "Net-(U5C-IN-)") (class "Default")
      (node (ref "R42") (pin "1") (pinfunction "1_1") (pintype "input"))
      (node (ref "R47") (pin "2") (pinfunction "2_2") (pintype "input"))
      (node (ref "U5") (pin "9") (pinfunction "IN-_9") (pintype "input"))
    )
    (net (code "78") (name "Net-(U5C-OUT)") (class "Default")
      (node (ref "R46") (pin "2") (pinfunction "2_2") (pintype "input"))
      (node (ref "U5") (pin "8") (pinfunction "OUT_8") (pintype "output"))
    )
    (net (code "79") (name "Net-(U5D-IN+)") (class "Default")
      (node (ref "C28") (pin "2") (pinfunction "2_2") (pintype "input"))
      (node (ref "R53") (pin "2") (pinfunction "2_2") (pintype "input"))
      (node (ref "R54") (pin "1") (pinfunction "1_1") (pintype "input"))
      (node (ref "U5") (pin "12") (pinfunction "IN+_12") (pintype "input"))
    )
    (net (code "80") (name "Net-(U5D-OUT)") (class "Default")
      (node (ref "U5") (pin "14") (pinfunction "OUT_14") (pintype "output"))
      (node (ref "U8") (pin "2") (pinfunction "CAT_2") (pintype "input"))
    )
    (net (code "81") (name "Net-(U6-COMP)") (class "Default")
      (node (ref "R43") (pin "2") (pinfunction "2_2") (pintype "input"))
      (node (ref "R48") (pin "2") (pinfunction "2_2") (pintype "input"))
      (node (ref "U6") (pin "5") (pinfunction "COMP_5") (pintype "input"))
    )
    (net (code "82") (name "Net-(U6-DRC)") (class "Default")
      (node (ref "R41") (pin "1") (pinfunction "1_1") (pintype "input"))
      (node (ref "U6") (pin "8") (pinfunction "DRC_8") (pintype "input"))
    )
    (net (code "83") (name "Net-(U6-IPK)") (class "Default")
      (node (ref "L1") (pin "1") (pinfunction "1_1") (pintype "unspecified"))
      (node (ref "R41") (pin "2") (pinfunction "2_2") (pintype "input"))
      (node (ref "R45") (pin "2") (pinfunction "2_2") (pintype "unspecified"))
      (node (ref "U6") (pin "7") (pinfunction "IPK_7") (pintype "input"))
    )
    (net (code "84") (name "Net-(U6-SWC)") (class "Default")
      (node (ref "L1") (pin "2") (pinfunction "2_2") (pintype "unspecified"))
      (node (ref "U6") (pin "1") (pinfunction "SWC_1") (pintype "input"))
      (node (ref "VD14") (pin "2") (pinfunction "A_2") (pintype "input"))
    )
    (net (code "85") (name "Net-(U6-TCAP)") (class "Default")
      (node (ref "C26") (pin "2") (pinfunction "2_2") (pintype "input"))
      (node (ref "U6") (pin "3") (pinfunction "TCAP_3") (pintype "input"))
    )
    (net (code "86") (name "Net-(U7-COMP)") (class "Default")
      (node (ref "R55") (pin "1") (pinfunction "1_1") (pintype "input"))
      (node (ref "R56") (pin "1") (pinfunction "1_1") (pintype "input"))
      (node (ref "U7") (pin "5") (pinfunction "COMP_5") (pintype "input"))
    )
    (net (code "87") (name "Net-(U7-DRC)") (class "Default")
      (node (ref "R52") (pin "2") (pinfunction "2_2") (pintype "input"))
      (node (ref "U7") (pin "1") (pinfunction "SWC_1") (pintype "input"))
      (node (ref "U7") (pin "7") (pinfunction "IPK_7") (pintype "input"))
      (node (ref "U7") (pin "8") (pinfunction "DRC_8") (pintype "input"))
    )
    (net (code "88") (name "Net-(U7-GND)") (class "Default")
      (node (ref "C29") (pin "1") (pinfunction "1_1") (pintype "input"))
      (node (ref "C30") (pin "2") (pinfunction "2_2") (pintype "input"))
      (node (ref "L4") (pin "1") (pinfunction "1_1") (pintype "input"))
      (node (ref "R55") (pin "2") (pinfunction "2_2") (pintype "input"))
      (node (ref "U7") (pin "4") (pinfunction "GND_4") (pintype "input"))
      (node (ref "VD16") (pin "2") (pinfunction "A_2") (pintype "input"))
    )
    (net (code "89") (name "Net-(U7-SWE)") (class "Default")
      (node (ref "L3") (pin "1") (pinfunction "1_1") (pintype "input"))
      (node (ref "U7") (pin "2") (pinfunction "SWE_2") (pintype "input"))
      (node (ref "VD16") (pin "1") (pinfunction "C_1") (pintype "input"))
    )
    (net (code "90") (name "Net-(U7-TCAP)") (class "Default")
      (node (ref "C29") (pin "2") (pinfunction "2_2") (pintype "input"))
      (node (ref "U7") (pin "3") (pinfunction "TCAP_3") (pintype "input"))
    )
    (net (code "91") (name "Net-(U8-AN)") (class "Default")
      (node (ref "R50") (pin "2") (pinfunction "2_2") (pintype "input"))
      (node (ref "U8") (pin "1") (pinfunction "AN_1") (pintype "input"))
    )
    (net (code "92") (name "Net-(U9-VIN)") (class "Default")
      (node (ref "C32") (pin "1") (pinfunction "1_1") (pintype "input"))
      (node (ref "R58") (pin "2") (pinfunction "2_2") (pintype "input"))
      (node (ref "U9") (pin "3") (pinfunction "VIN_3") (pintype "input"))
    )
    (net (code "93") (name "Net-(VD1-C)") (class "Default")
      (node (ref "K1") (pin "4") (pinfunction "4_4") (pintype "input"))
      (node (ref "VD1") (pin "1") (pinfunction "C_1") (pintype "input"))
      (node (ref "VT1") (pin "3") (pinfunction "C_3") (pintype "input"))
    )
    (net (code "94") (name "Net-(VD2-C)") (class "Default")
      (node (ref "K2") (pin "4") (pinfunction "4_4") (pintype "input"))
      (node (ref "VD2") (pin "1") (pinfunction "C_1") (pintype "input"))
      (node (ref "VT2") (pin "3") (pinfunction "C_3") (pintype "input"))
    )
    (net (code "95") (name "Net-(VD3-C)") (class "Default")
      (node (ref "K3") (pin "4") (pinfunction "4_4") (pintype "input"))
      (node (ref "VD3") (pin "1") (pinfunction "C_1") (pintype "input"))
      (node (ref "VT3") (pin "3") (pinfunction "C_3") (pintype "input"))
    )
    (net (code "96") (name "Net-(VD4-C)") (class "Default")
      (node (ref "K4") (pin "4") (pinfunction "4_4") (pintype "input"))
      (node (ref "VD4") (pin "1") (pinfunction "C_1") (pintype "input"))
      (node (ref "VT4") (pin "3") (pinfunction "C_3") (pintype "input"))
    )
    (net (code "97") (name "Net-(VD6-C)") (class "Default")
      (node (ref "R17") (pin "1") (pinfunction "1_1") (pintype "input"))
      (node (ref "RP2") (pin "1") (pinfunction "1_1") (pintype "input"))
      (node (ref "VD6") (pin "1") (pinfunction "C_1") (pintype "input"))
      (node (ref "VD7") (pin "2") (pinfunction "A_2") (pintype "input"))
    )
    (net (code "98") (name "Net-(VD13-A)") (class "Default")
      (node (ref "R31") (pin "1") (pinfunction "1_1") (pintype "input"))
      (node (ref "R36") (pin "1") (pinfunction "1_1") (pintype "input"))
      (node (ref "VD13") (pin "2") (pinfunction "A_2") (pintype "input"))
    )
    (net (code "99") (name "Net-(VD14-C)") (class "Default")
      (node (ref "C24") (pin "1") (pinfunction "1_1") (pintype "input"))
      (node (ref "L2") (pin "1") (pinfunction "1_1") (pintype "input"))
      (node (ref "R43") (pin "1") (pinfunction "1_1") (pintype "input"))
      (node (ref "VD14") (pin "1") (pinfunction "C_1") (pintype "input"))
    )
    (net (code "100") (name "Net-(VT1-B)") (class "Default")
      (node (ref "R6") (pin "2") (pinfunction "2_2") (pintype "input"))
      (node (ref "VT1") (pin "1") (pinfunction "B_1") (pintype "input"))
    )
    (net (code "101") (name "Net-(VT2-B)") (class "Default")
      (node (ref "R7") (pin "2") (pinfunction "2_2") (pintype "input"))
      (node (ref "VT2") (pin "1") (pinfunction "B_1") (pintype "input"))
    )
    (net (code "102") (name "Net-(VT3-B)") (class "Default")
      (node (ref "R8") (pin "2") (pinfunction "2_2") (pintype "input"))
      (node (ref "VT3") (pin "1") (pinfunction "B_1") (pintype "input"))
    )
    (net (code "103") (name "Net-(VT4-B)") (class "Default")
      (node (ref "R9") (pin "2") (pinfunction "2_2") (pintype "input"))
      (node (ref "VT4") (pin "1") (pinfunction "B_1") (pintype "input"))
    )
    (net (code "104") (name "Net-(VT5-B)") (class "Default")
      (node (ref "R29") (pin "1") (pinfunction "1_1") (pintype "input"))
      (node (ref "VT5") (pin "1") (pinfunction "B_1") (pintype "input"))
    )
    (net (code "105") (name "Net-(VT6-B)") (class "Default")
      (node (ref "R30") (pin "1") (pinfunction "1_1") (pintype "input"))
      (node (ref "VT6") (pin "1") (pinfunction "B_1") (pintype "input"))
    )
    (net (code "106") (name "Net-(VT6-C)") (class "Default")
      (node (ref "R57") (pin "2") (pinfunction "2_2") (pintype "input"))
      (node (ref "VT6") (pin "3") (pinfunction "C_3") (pintype "input"))
    )
    (net (code "107") (name "VCC") (class "Default")
      (node (ref "C1") (pin "2") (pinfunction "2_2") (pintype "input"))
      (node (ref "C10") (pin "2") (pinfunction "2_2") (pintype "input"))
      (node (ref "C11") (pin "2") (pinfunction "2_2") (pintype "input"))
      (node (ref "C12") (pin "1") (pinfunction "1_1") (pintype "input"))
      (node (ref "C2") (pin "1") (pinfunction "1_1") (pintype "input"))
      (node (ref "C3") (pin "2") (pinfunction "2_2") (pintype "input"))
      (node (ref "C33") (pin "1") (pinfunction "1_1") (pintype "input"))
      (node (ref "C4") (pin "1") (pinfunction "1_1") (pintype "input"))
      (node (ref "LCD1") (pin "2") (pinfunction "VDD_2") (pintype "input"))
      (node (ref "R10") (pin "1") (pinfunction "1_1") (pintype "input"))
      (node (ref "R2") (pin "2") (pinfunction "2_2") (pintype "input"))
      (node (ref "R23") (pin "1") (pinfunction "1_1") (pintype "input"))
      (node (ref "R26") (pin "1") (pinfunction "1_1") (pintype "input"))
      (node (ref "R27") (pin "1") (pinfunction "1_1") (pintype "input"))
      (node (ref "R3") (pin "2") (pinfunction "2_2") (pintype "input"))
      (node (ref "R4") (pin "2") (pinfunction "2_2") (pintype "input"))
      (node (ref "R5") (pin "2") (pinfunction "2_2") (pintype "input"))
      (node (ref "R51") (pin "1") (pinfunction "1_1") (pintype "input"))
      (node (ref "RN1") (pin "1") (pinfunction "1_1") (pintype "input"))
      (node (ref "RP1") (pin "3") (pinfunction "3_3") (pintype "input"))
      (node (ref "T1") (pin "1") (pinfunction "1_1") (pintype "unspecified"))
      (node (ref "U1") (pin "40") (pinfunction "VCC_40") (pintype "input"))
      (node (ref "U4") (pin "16") (pinfunction "VCC_16") (pintype "input"))
      (node (ref "U9") (pin "2") (pinfunction "VOUT_2") (pintype "input"))
      (node (ref "U9") (pin "4") (pinfunction "VOUT_4") (pintype "input"))
      (node (ref "VT1") (pin "2") (pinfunction "E_2") (pintype "input"))
      (node (ref "VT2") (pin "2") (pinfunction "E_2") (pintype "input"))
      (node (ref "VT3") (pin "2") (pinfunction "E_2") (pintype "input"))
      (node (ref "VT4") (pin "2") (pinfunction "E_2") (pintype "input"))
      (node (ref "VT5") (pin "2") (pinfunction "E_2") (pintype "input"))
      (node (ref "VT6") (pin "2") (pinfunction "E_2") (pintype "input"))
    )
    (net (code "108") (name "VIN") (class "Default")
      (node (ref "C25") (pin "1") (pinfunction "1_1") (pintype "input"))
      (node (ref "C27") (pin "1") (pinfunction "1_1") (pintype "input"))
      (node (ref "F1") (pin "2") (pinfunction "2_2") (pintype "input"))
      (node (ref "R16") (pin "1") (pinfunction "1_1") (pintype "input"))
      (node (ref "R45") (pin "1") (pinfunction "1_1") (pintype "unspecified"))
      (node (ref "R52") (pin "1") (pinfunction "1_1") (pintype "input"))
      (node (ref "R58") (pin "1") (pinfunction "1_1") (pintype "input"))
      (node (ref "U6") (pin "6") (pinfunction "VCC_6") (pintype "input"))
      (node (ref "U7") (pin "6") (pinfunction "VCC_6") (pintype "input"))
    )
    (net (code "109") (name "unconnected-(J3-MH1-Pad10)") (class "Default")
      (node (ref "J3") (pin "10") (pinfunction "MH1_10") (pintype "input+no_connect"))
    )
    (net (code "110") (name "unconnected-(J3-MH2-Pad11)") (class "Default")
      (node (ref "J3") (pin "11") (pinfunction "MH2_11") (pintype "input+no_connect"))
    )
    (net (code "111") (name "unconnected-(J3-Pad1)") (class "Default")
      (node (ref "J3") (pin "1") (pinfunction "1_1") (pintype "input+no_connect"))
    )
    (net (code "112") (name "unconnected-(J3-Pad4)") (class "Default")
      (node (ref "J3") (pin "4") (pinfunction "4_4") (pintype "input+no_connect"))
    )
    (net (code "113") (name "unconnected-(J3-Pad6)") (class "Default")
      (node (ref "J3") (pin "6") (pinfunction "6_6") (pintype "input+no_connect"))
    )
    (net (code "114") (name "unconnected-(J3-Pad7)") (class "Default")
      (node (ref "J3") (pin "7") (pinfunction "7_7") (pintype "input+no_connect"))
    )
    (net (code "115") (name "unconnected-(J3-Pad8)") (class "Default")
      (node (ref "J3") (pin "8") (pinfunction "8_8") (pintype "input+no_connect"))
    )
    (net (code "116") (name "unconnected-(J3-Pad9)") (class "Default")
      (node (ref "J3") (pin "9") (pinfunction "9_9") (pintype "input+no_connect"))
    )
    (net (code "117") (name "unconnected-(K1-Pad2)") (class "Default")
      (node (ref "K1") (pin "2") (pinfunction "2_2") (pintype "input+no_connect"))
    )
    (net (code "118") (name "unconnected-(K2-Pad2)") (class "Default")
      (node (ref "K2") (pin "2") (pinfunction "2_2") (pintype "input+no_connect"))
    )
    (net (code "119") (name "unconnected-(K3-Pad2)") (class "Default")
      (node (ref "K3") (pin "2") (pinfunction "2_2") (pintype "input+no_connect"))
    )
    (net (code "120") (name "unconnected-(K4-Pad2)") (class "Default")
      (node (ref "K4") (pin "2") (pinfunction "2_2") (pintype "input+no_connect"))
    )
    (net (code "121") (name "unconnected-(P1-Pad2)") (class "Default")
      (node (ref "P1") (pin "2") (pinfunction "2_2") (pintype "input+no_connect"))
    )
    (net (code "122") (name "unconnected-(S1-A-Pad1)") (class "Default")
      (node (ref "S1") (pin "1") (pinfunction "A_1") (pintype "input+no_connect"))
    )
    (net (code "123") (name "unconnected-(S1-D-Pad4)") (class "Default")
      (node (ref "S1") (pin "4") (pinfunction "D_4") (pintype "input+no_connect"))
    )
    (net (code "124") (name "unconnected-(S2-A-Pad1)") (class "Default")
      (node (ref "S2") (pin "1") (pinfunction "A_1") (pintype "input+no_connect"))
    )
    (net (code "125") (name "unconnected-(S2-D-Pad4)") (class "Default")
      (node (ref "S2") (pin "4") (pinfunction "D_4") (pintype "input+no_connect"))
    )
    (net (code "126") (name "unconnected-(S3-A-Pad1)") (class "Default")
      (node (ref "S3") (pin "1") (pinfunction "A_1") (pintype "input+no_connect"))
    )
    (net (code "127") (name "unconnected-(S3-D-Pad4)") (class "Default")
      (node (ref "S3") (pin "4") (pinfunction "D_4") (pintype "input+no_connect"))
    )
    (net (code "128") (name "unconnected-(S4-A-Pad1)") (class "Default")
      (node (ref "S4") (pin "1") (pinfunction "A_1") (pintype "input+no_connect"))
    )
    (net (code "129") (name "unconnected-(S4-D-Pad4)") (class "Default")
      (node (ref "S4") (pin "4") (pinfunction "D_4") (pintype "input+no_connect"))
    )
    (net (code "130") (name "unconnected-(S5-A-Pad1)") (class "Default")
      (node (ref "S5") (pin "1") (pinfunction "A_1") (pintype "input+no_connect"))
    )
    (net (code "131") (name "unconnected-(S5-D-Pad4)") (class "Default")
      (node (ref "S5") (pin "4") (pinfunction "D_4") (pintype "input+no_connect"))
    )
    (net (code "132") (name "unconnected-(S6-A-Pad1)") (class "Default")
      (node (ref "S6") (pin "1") (pinfunction "A_1") (pintype "input+no_connect"))
    )
    (net (code "133") (name "unconnected-(S6-D-Pad4)") (class "Default")
      (node (ref "S6") (pin "4") (pinfunction "D_4") (pintype "input+no_connect"))
    )
    (net (code "134") (name "unconnected-(S7-Pad3)") (class "Default")
      (node (ref "S7") (pin "3") (pinfunction "3_3") (pintype "input+no_connect"))
    )
    (net (code "135") (name "unconnected-(S7-Pad4)") (class "Default")
      (node (ref "S7") (pin "4") (pinfunction "4_4") (pintype "input+no_connect"))
    )
    (net (code "136") (name "unconnected-(S7-Pad5)") (class "Default")
      (node (ref "S7") (pin "5") (pinfunction "5_5") (pintype "input+no_connect"))
    )
    (net (code "137") (name "unconnected-(S7-Pad6)") (class "Default")
      (node (ref "S7") (pin "6") (pinfunction "6_6") (pintype "input+no_connect"))
    )
    (net (code "138") (name "unconnected-(U1-ALE{slash}P4.5-Pad30)") (class "Default")
      (node (ref "U1") (pin "30") (pinfunction "ALE/P4.5_30") (pintype "input+no_connect"))
    )
    (net (code "139") (name "unconnected-(U1-NA{slash}P4.4-Pad29)") (class "Default")
      (node (ref "U1") (pin "29") (pinfunction "NA/P4.4_29") (pintype "input+no_connect"))
    )
    (net (code "140") (name "unconnected-(U1-P2.0{slash}A8-Pad21)") (class "Default")
      (node (ref "U1") (pin "21") (pinfunction "P2.0/A8_21") (pintype "input+no_connect"))
    )
    (net (code "141") (name "unconnected-(U1-P2.1{slash}A9-Pad22)") (class "Default")
      (node (ref "U1") (pin "22") (pinfunction "P2.1/A9_22") (pintype "input+no_connect"))
    )
    (net (code "142") (name "unconnected-(U4-R2IN-Pad8)") (class "Default")
      (node (ref "U4") (pin "8") (pinfunction "R2IN_8") (pintype "input+no_connect"))
    )
    (net (code "143") (name "unconnected-(U4-R2OUT-Pad9)") (class "Default")
      (node (ref "U4") (pin "9") (pinfunction "R2OUT_9") (pintype "input+no_connect"))
    )
    (net (code "144") (name "unconnected-(U4-T2IN-Pad10)") (class "Default")
      (node (ref "U4") (pin "10") (pinfunction "T2IN_10") (pintype "input+no_connect"))
    )
    (net (code "145") (name "unconnected-(U4-T2OUT-Pad7)") (class "Default")
      (node (ref "U4") (pin "7") (pinfunction "T2OUT_7") (pintype "input+no_connect"))
    )
  )
)
